# VDD_GND.net
KiCad netlist of a schematic drawn in Altium Designer
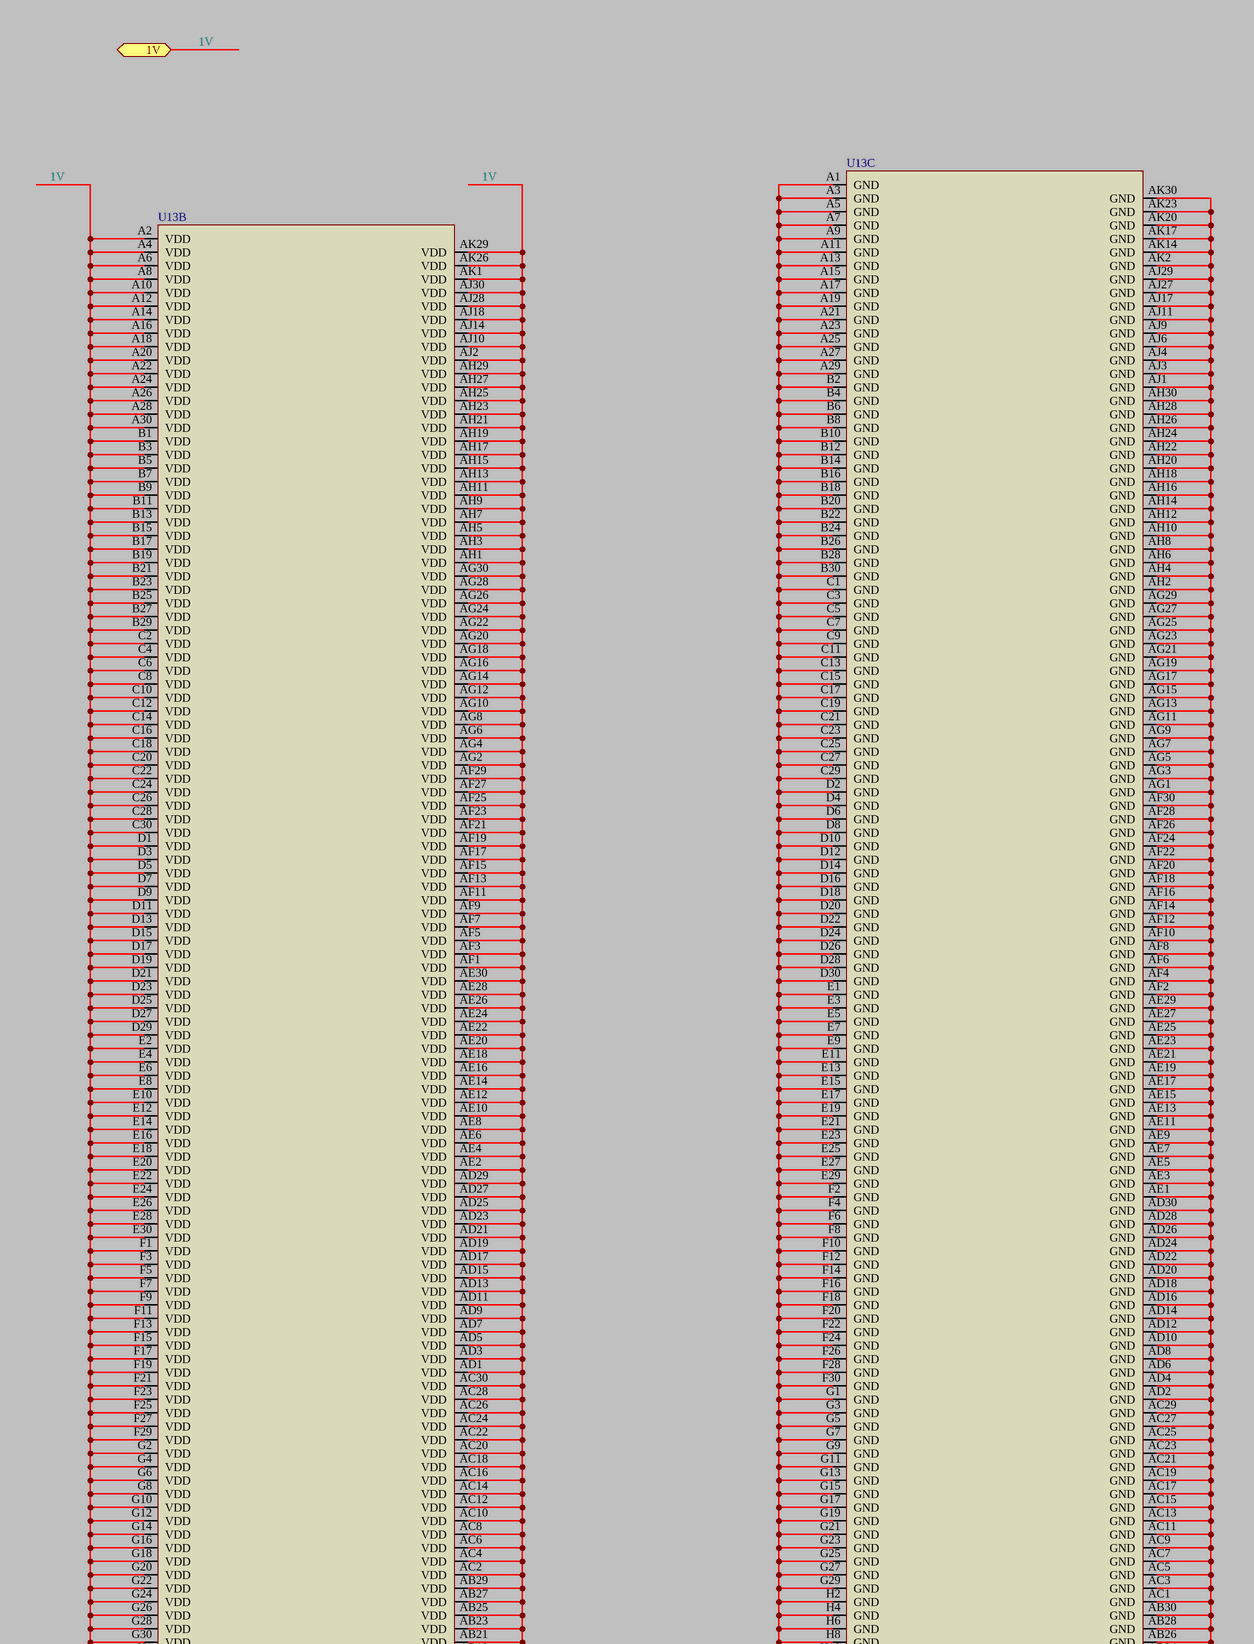
[diagram p0: VDD_GND.SchDoc, top left]
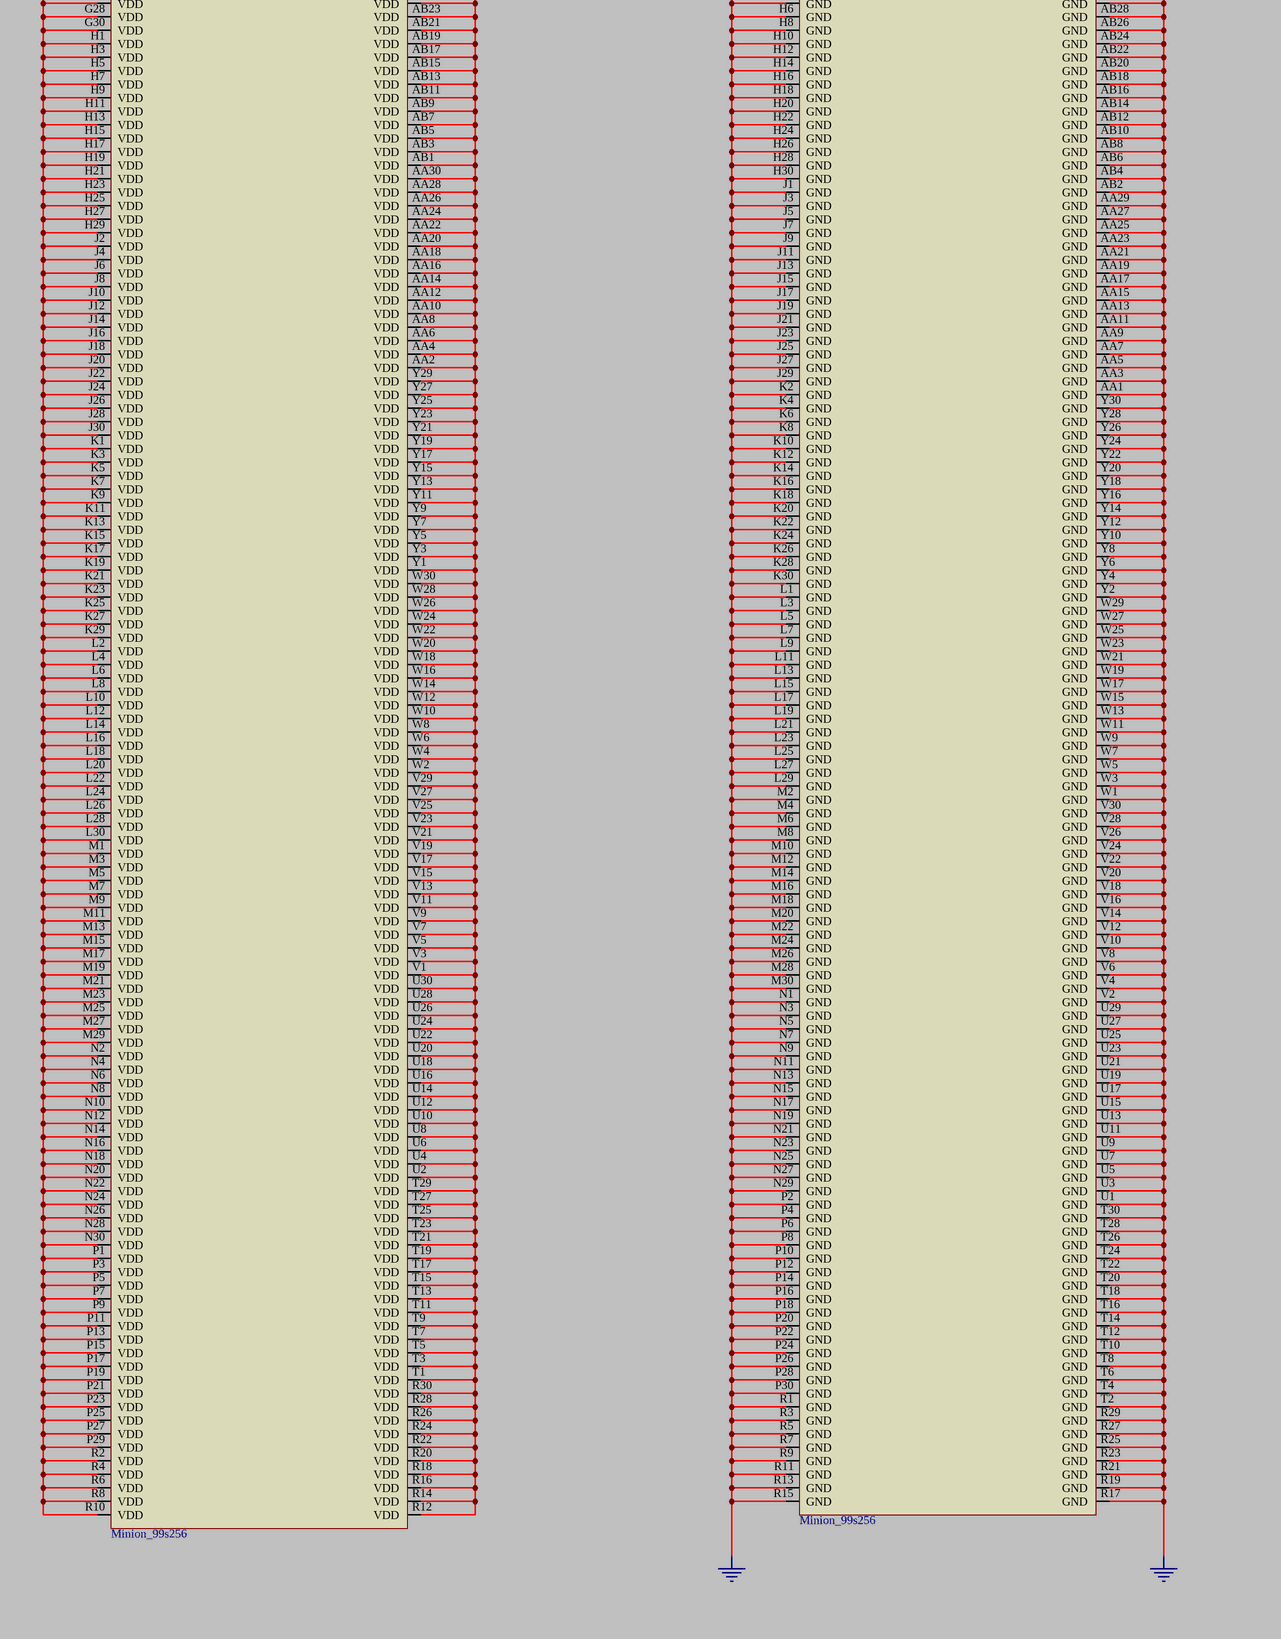
[diagram p1: VDD_GND.SchDoc, bottom left]
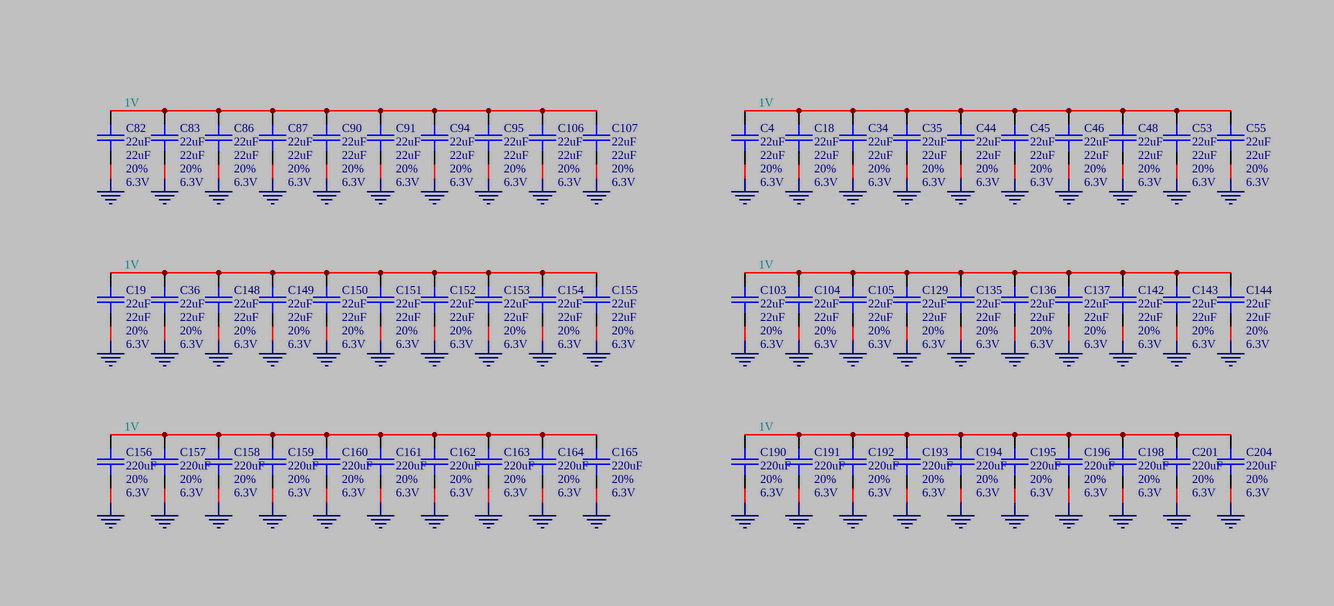
[diagram p2: VDD_GND.SchDoc, bottom middle]
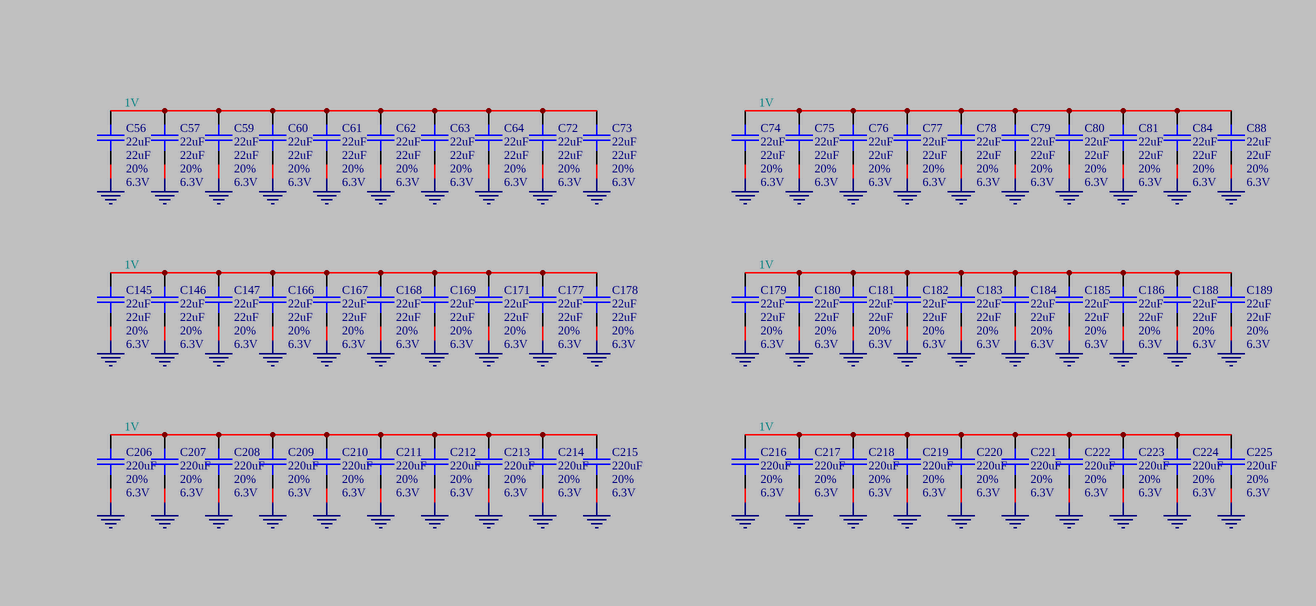
[diagram p3: VDD_GND.SchDoc, bottom right]

(export (version "E")
  (design (tool "Eeschema 10.0.6"))
  (components
    (comp (ref "C4")
      (value "22uF")
      (footprint "SMD_0805_CAPC2012X145N")
      (fields
        (field (name "DB_PART_NUMBER") "CAP000043686")
        (field (name "DB_VALUE") "22uF")
        (field (name "DB_TOLERANCE") "20%")
        (field (name "DB_VOLTAGE") "6.3V")
        (field (name "DB_MANUFACTURER_PART") "KEMET    C0805C226M9PAC")
        (field (name "DB_APPROVED_BY") "ISHIDDEN=T")
      )
      (libsource (lib "Database_Libs1") (part "C"))
    )
    (comp (ref "C18")
      (value "22uF")
      (footprint "SMD_0805_CAPC2012X145N")
      (fields
        (field (name "DB_PART_NUMBER") "CAP000043686")
        (field (name "DB_VALUE") "22uF")
        (field (name "DB_TOLERANCE") "20%")
        (field (name "DB_VOLTAGE") "6.3V")
        (field (name "DB_MANUFACTURER_PART") "KEMET    C0805C226M9PAC")
        (field (name "DB_APPROVED_BY") "ISHIDDEN=T")
      )
      (libsource (lib "Database_Libs1") (part "C"))
    )
    (comp (ref "C19")
      (value "22uF")
      (footprint "SMD_0805_CAPC2012X145N")
      (fields
        (field (name "DB_PART_NUMBER") "CAP000043686")
        (field (name "DB_VALUE") "22uF")
        (field (name "DB_TOLERANCE") "20%")
        (field (name "DB_VOLTAGE") "6.3V")
        (field (name "DB_MANUFACTURER_PART") "KEMET    C0805C226M9PAC")
        (field (name "DB_APPROVED_BY") "ISHIDDEN=T")
      )
      (libsource (lib "Database_Libs1") (part "C"))
    )
    (comp (ref "C34")
      (value "22uF")
      (footprint "SMD_0805_CAPC2012X145N")
      (fields
        (field (name "DB_PART_NUMBER") "CAP000043686")
        (field (name "DB_VALUE") "22uF")
        (field (name "DB_TOLERANCE") "20%")
        (field (name "DB_VOLTAGE") "6.3V")
        (field (name "DB_MANUFACTURER_PART") "KEMET    C0805C226M9PAC")
        (field (name "DB_APPROVED_BY") "ISHIDDEN=T")
      )
      (libsource (lib "Database_Libs1") (part "C"))
    )
    (comp (ref "C35")
      (value "22uF")
      (footprint "SMD_0805_CAPC2012X145N")
      (fields
        (field (name "DB_PART_NUMBER") "CAP000043686")
        (field (name "DB_VALUE") "22uF")
        (field (name "DB_TOLERANCE") "20%")
        (field (name "DB_VOLTAGE") "6.3V")
        (field (name "DB_MANUFACTURER_PART") "KEMET    C0805C226M9PAC")
        (field (name "DB_APPROVED_BY") "ISHIDDEN=T")
      )
      (libsource (lib "Database_Libs1") (part "C"))
    )
    (comp (ref "C36")
      (value "22uF")
      (footprint "SMD_0805_CAPC2012X145N")
      (fields
        (field (name "DB_PART_NUMBER") "CAP000043686")
        (field (name "DB_VALUE") "22uF")
        (field (name "DB_TOLERANCE") "20%")
        (field (name "DB_VOLTAGE") "6.3V")
        (field (name "DB_MANUFACTURER_PART") "KEMET    C0805C226M9PAC")
        (field (name "DB_APPROVED_BY") "ISHIDDEN=T")
      )
      (libsource (lib "Database_Libs1") (part "C"))
    )
    (comp (ref "C44")
      (value "22uF")
      (footprint "SMD_0805_CAPC2012X145N")
      (fields
        (field (name "DB_PART_NUMBER") "CAP000043686")
        (field (name "DB_VALUE") "22uF")
        (field (name "DB_TOLERANCE") "20%")
        (field (name "DB_VOLTAGE") "6.3V")
        (field (name "DB_MANUFACTURER_PART") "KEMET    C0805C226M9PAC")
        (field (name "DB_APPROVED_BY") "ISHIDDEN=T")
      )
      (libsource (lib "Database_Libs1") (part "C"))
    )
    (comp (ref "C45")
      (value "22uF")
      (footprint "SMD_0805_CAPC2012X145N")
      (fields
        (field (name "DB_PART_NUMBER") "CAP000043686")
        (field (name "DB_VALUE") "22uF")
        (field (name "DB_TOLERANCE") "20%")
        (field (name "DB_VOLTAGE") "6.3V")
        (field (name "DB_MANUFACTURER_PART") "KEMET    C0805C226M9PAC")
        (field (name "DB_APPROVED_BY") "ISHIDDEN=T")
      )
      (libsource (lib "Database_Libs1") (part "C"))
    )
    (comp (ref "C46")
      (value "22uF")
      (footprint "SMD_0805_CAPC2012X145N")
      (fields
        (field (name "DB_PART_NUMBER") "CAP000043686")
        (field (name "DB_VALUE") "22uF")
        (field (name "DB_TOLERANCE") "20%")
        (field (name "DB_VOLTAGE") "6.3V")
        (field (name "DB_MANUFACTURER_PART") "KEMET    C0805C226M9PAC")
        (field (name "DB_APPROVED_BY") "ISHIDDEN=T")
      )
      (libsource (lib "Database_Libs1") (part "C"))
    )
    (comp (ref "C48")
      (value "22uF")
      (footprint "SMD_0805_CAPC2012X145N")
      (fields
        (field (name "DB_PART_NUMBER") "CAP000043686")
        (field (name "DB_VALUE") "22uF")
        (field (name "DB_TOLERANCE") "20%")
        (field (name "DB_VOLTAGE") "6.3V")
        (field (name "DB_MANUFACTURER_PART") "KEMET    C0805C226M9PAC")
        (field (name "DB_APPROVED_BY") "ISHIDDEN=T")
      )
      (libsource (lib "Database_Libs1") (part "C"))
    )
    (comp (ref "C53")
      (value "22uF")
      (footprint "SMD_0805_CAPC2012X145N")
      (fields
        (field (name "DB_PART_NUMBER") "CAP000043686")
        (field (name "DB_VALUE") "22uF")
        (field (name "DB_TOLERANCE") "20%")
        (field (name "DB_VOLTAGE") "6.3V")
        (field (name "DB_MANUFACTURER_PART") "KEMET    C0805C226M9PAC")
        (field (name "DB_APPROVED_BY") "ISHIDDEN=T")
      )
      (libsource (lib "Database_Libs1") (part "C"))
    )
    (comp (ref "C55")
      (value "22uF")
      (footprint "SMD_0805_CAPC2012X145N")
      (fields
        (field (name "DB_PART_NUMBER") "CAP000043686")
        (field (name "DB_VALUE") "22uF")
        (field (name "DB_TOLERANCE") "20%")
        (field (name "DB_VOLTAGE") "6.3V")
        (field (name "DB_MANUFACTURER_PART") "KEMET    C0805C226M9PAC")
        (field (name "DB_APPROVED_BY") "ISHIDDEN=T")
      )
      (libsource (lib "Database_Libs1") (part "C"))
    )
    (comp (ref "C56")
      (value "22uF")
      (footprint "SMD_0805_CAPC2012X145N")
      (fields
        (field (name "DB_PART_NUMBER") "CAP000043686")
        (field (name "DB_VALUE") "22uF")
        (field (name "DB_TOLERANCE") "20%")
        (field (name "DB_VOLTAGE") "6.3V")
        (field (name "DB_MANUFACTURER_PART") "KEMET    C0805C226M9PAC")
        (field (name "DB_APPROVED_BY") "ISHIDDEN=T")
      )
      (libsource (lib "Database_Libs1") (part "C"))
    )
    (comp (ref "C57")
      (value "22uF")
      (footprint "SMD_0805_CAPC2012X145N")
      (fields
        (field (name "DB_PART_NUMBER") "CAP000043686")
        (field (name "DB_VALUE") "22uF")
        (field (name "DB_TOLERANCE") "20%")
        (field (name "DB_VOLTAGE") "6.3V")
        (field (name "DB_MANUFACTURER_PART") "KEMET    C0805C226M9PAC")
        (field (name "DB_APPROVED_BY") "ISHIDDEN=T")
      )
      (libsource (lib "Database_Libs1") (part "C"))
    )
    (comp (ref "C59")
      (value "22uF")
      (footprint "SMD_0805_CAPC2012X145N")
      (fields
        (field (name "DB_PART_NUMBER") "CAP000043686")
        (field (name "DB_VALUE") "22uF")
        (field (name "DB_TOLERANCE") "20%")
        (field (name "DB_VOLTAGE") "6.3V")
        (field (name "DB_MANUFACTURER_PART") "KEMET    C0805C226M9PAC")
        (field (name "DB_APPROVED_BY") "ISHIDDEN=T")
      )
      (libsource (lib "Database_Libs1") (part "C"))
    )
    (comp (ref "C60")
      (value "22uF")
      (footprint "SMD_0805_CAPC2012X145N")
      (fields
        (field (name "DB_PART_NUMBER") "CAP000043686")
        (field (name "DB_VALUE") "22uF")
        (field (name "DB_TOLERANCE") "20%")
        (field (name "DB_VOLTAGE") "6.3V")
        (field (name "DB_MANUFACTURER_PART") "KEMET    C0805C226M9PAC")
        (field (name "DB_APPROVED_BY") "ISHIDDEN=T")
      )
      (libsource (lib "Database_Libs1") (part "C"))
    )
    (comp (ref "C61")
      (value "22uF")
      (footprint "SMD_0805_CAPC2012X145N")
      (fields
        (field (name "DB_PART_NUMBER") "CAP000043686")
        (field (name "DB_VALUE") "22uF")
        (field (name "DB_TOLERANCE") "20%")
        (field (name "DB_VOLTAGE") "6.3V")
        (field (name "DB_MANUFACTURER_PART") "KEMET    C0805C226M9PAC")
        (field (name "DB_APPROVED_BY") "ISHIDDEN=T")
      )
      (libsource (lib "Database_Libs1") (part "C"))
    )
    (comp (ref "C62")
      (value "22uF")
      (footprint "SMD_0805_CAPC2012X145N")
      (fields
        (field (name "DB_PART_NUMBER") "CAP000043686")
        (field (name "DB_VALUE") "22uF")
        (field (name "DB_TOLERANCE") "20%")
        (field (name "DB_VOLTAGE") "6.3V")
        (field (name "DB_MANUFACTURER_PART") "KEMET    C0805C226M9PAC")
        (field (name "DB_APPROVED_BY") "ISHIDDEN=T")
      )
      (libsource (lib "Database_Libs1") (part "C"))
    )
    (comp (ref "C63")
      (value "22uF")
      (footprint "SMD_0805_CAPC2012X145N")
      (fields
        (field (name "DB_PART_NUMBER") "CAP000043686")
        (field (name "DB_VALUE") "22uF")
        (field (name "DB_TOLERANCE") "20%")
        (field (name "DB_VOLTAGE") "6.3V")
        (field (name "DB_MANUFACTURER_PART") "KEMET    C0805C226M9PAC")
        (field (name "DB_APPROVED_BY") "ISHIDDEN=T")
      )
      (libsource (lib "Database_Libs1") (part "C"))
    )
    (comp (ref "C64")
      (value "22uF")
      (footprint "SMD_0805_CAPC2012X145N")
      (fields
        (field (name "DB_PART_NUMBER") "CAP000043686")
        (field (name "DB_VALUE") "22uF")
        (field (name "DB_TOLERANCE") "20%")
        (field (name "DB_VOLTAGE") "6.3V")
        (field (name "DB_MANUFACTURER_PART") "KEMET    C0805C226M9PAC")
        (field (name "DB_APPROVED_BY") "ISHIDDEN=T")
      )
      (libsource (lib "Database_Libs1") (part "C"))
    )
    (comp (ref "C72")
      (value "22uF")
      (footprint "SMD_0805_CAPC2012X145N")
      (fields
        (field (name "DB_PART_NUMBER") "CAP000043686")
        (field (name "DB_VALUE") "22uF")
        (field (name "DB_TOLERANCE") "20%")
        (field (name "DB_VOLTAGE") "6.3V")
        (field (name "DB_MANUFACTURER_PART") "KEMET    C0805C226M9PAC")
        (field (name "DB_APPROVED_BY") "ISHIDDEN=T")
      )
      (libsource (lib "Database_Libs1") (part "C"))
    )
    (comp (ref "C73")
      (value "22uF")
      (footprint "SMD_0805_CAPC2012X145N")
      (fields
        (field (name "DB_PART_NUMBER") "CAP000043686")
        (field (name "DB_VALUE") "22uF")
        (field (name "DB_TOLERANCE") "20%")
        (field (name "DB_VOLTAGE") "6.3V")
        (field (name "DB_MANUFACTURER_PART") "KEMET    C0805C226M9PAC")
        (field (name "DB_APPROVED_BY") "ISHIDDEN=T")
      )
      (libsource (lib "Database_Libs1") (part "C"))
    )
    (comp (ref "C74")
      (value "22uF")
      (footprint "SMD_0805_CAPC2012X145N")
      (fields
        (field (name "DB_PART_NUMBER") "CAP000043686")
        (field (name "DB_VALUE") "22uF")
        (field (name "DB_TOLERANCE") "20%")
        (field (name "DB_VOLTAGE") "6.3V")
        (field (name "DB_MANUFACTURER_PART") "KEMET    C0805C226M9PAC")
        (field (name "DB_APPROVED_BY") "ISHIDDEN=T")
      )
      (libsource (lib "Database_Libs1") (part "C"))
    )
    (comp (ref "C75")
      (value "22uF")
      (footprint "SMD_0805_CAPC2012X145N")
      (fields
        (field (name "DB_PART_NUMBER") "CAP000043686")
        (field (name "DB_VALUE") "22uF")
        (field (name "DB_TOLERANCE") "20%")
        (field (name "DB_VOLTAGE") "6.3V")
        (field (name "DB_MANUFACTURER_PART") "KEMET    C0805C226M9PAC")
        (field (name "DB_APPROVED_BY") "ISHIDDEN=T")
      )
      (libsource (lib "Database_Libs1") (part "C"))
    )
    (comp (ref "C76")
      (value "22uF")
      (footprint "SMD_0805_CAPC2012X145N")
      (fields
        (field (name "DB_PART_NUMBER") "CAP000043686")
        (field (name "DB_VALUE") "22uF")
        (field (name "DB_TOLERANCE") "20%")
        (field (name "DB_VOLTAGE") "6.3V")
        (field (name "DB_MANUFACTURER_PART") "KEMET    C0805C226M9PAC")
        (field (name "DB_APPROVED_BY") "ISHIDDEN=T")
      )
      (libsource (lib "Database_Libs1") (part "C"))
    )
    (comp (ref "C77")
      (value "22uF")
      (footprint "SMD_0805_CAPC2012X145N")
      (fields
        (field (name "DB_PART_NUMBER") "CAP000043686")
        (field (name "DB_VALUE") "22uF")
        (field (name "DB_TOLERANCE") "20%")
        (field (name "DB_VOLTAGE") "6.3V")
        (field (name "DB_MANUFACTURER_PART") "KEMET    C0805C226M9PAC")
        (field (name "DB_APPROVED_BY") "ISHIDDEN=T")
      )
      (libsource (lib "Database_Libs1") (part "C"))
    )
    (comp (ref "C78")
      (value "22uF")
      (footprint "SMD_0805_CAPC2012X145N")
      (fields
        (field (name "DB_PART_NUMBER") "CAP000043686")
        (field (name "DB_VALUE") "22uF")
        (field (name "DB_TOLERANCE") "20%")
        (field (name "DB_VOLTAGE") "6.3V")
        (field (name "DB_MANUFACTURER_PART") "KEMET    C0805C226M9PAC")
        (field (name "DB_APPROVED_BY") "ISHIDDEN=T")
      )
      (libsource (lib "Database_Libs1") (part "C"))
    )
    (comp (ref "C79")
      (value "22uF")
      (footprint "SMD_0805_CAPC2012X145N")
      (fields
        (field (name "DB_PART_NUMBER") "CAP000043686")
        (field (name "DB_VALUE") "22uF")
        (field (name "DB_TOLERANCE") "20%")
        (field (name "DB_VOLTAGE") "6.3V")
        (field (name "DB_MANUFACTURER_PART") "KEMET    C0805C226M9PAC")
        (field (name "DB_APPROVED_BY") "ISHIDDEN=T")
      )
      (libsource (lib "Database_Libs1") (part "C"))
    )
    (comp (ref "C80")
      (value "22uF")
      (footprint "SMD_0805_CAPC2012X145N")
      (fields
        (field (name "DB_PART_NUMBER") "CAP000043686")
        (field (name "DB_VALUE") "22uF")
        (field (name "DB_TOLERANCE") "20%")
        (field (name "DB_VOLTAGE") "6.3V")
        (field (name "DB_MANUFACTURER_PART") "KEMET    C0805C226M9PAC")
        (field (name "DB_APPROVED_BY") "ISHIDDEN=T")
      )
      (libsource (lib "Database_Libs1") (part "C"))
    )
    (comp (ref "C81")
      (value "22uF")
      (footprint "SMD_0805_CAPC2012X145N")
      (fields
        (field (name "DB_PART_NUMBER") "CAP000043686")
        (field (name "DB_VALUE") "22uF")
        (field (name "DB_TOLERANCE") "20%")
        (field (name "DB_VOLTAGE") "6.3V")
        (field (name "DB_MANUFACTURER_PART") "KEMET    C0805C226M9PAC")
        (field (name "DB_APPROVED_BY") "ISHIDDEN=T")
      )
      (libsource (lib "Database_Libs1") (part "C"))
    )
    (comp (ref "C82")
      (value "22uF")
      (footprint "SMD_0805_CAPC2012X145N")
      (fields
        (field (name "DB_PART_NUMBER") "CAP000043686")
        (field (name "DB_VALUE") "22uF")
        (field (name "DB_TOLERANCE") "20%")
        (field (name "DB_VOLTAGE") "6.3V")
        (field (name "DB_MANUFACTURER_PART") "KEMET    C0805C226M9PAC")
        (field (name "DB_APPROVED_BY") "ISHIDDEN=T")
      )
      (libsource (lib "Database_Libs1") (part "C"))
    )
    (comp (ref "C83")
      (value "22uF")
      (footprint "SMD_0805_CAPC2012X145N")
      (fields
        (field (name "DB_PART_NUMBER") "CAP000043686")
        (field (name "DB_VALUE") "22uF")
        (field (name "DB_TOLERANCE") "20%")
        (field (name "DB_VOLTAGE") "6.3V")
        (field (name "DB_MANUFACTURER_PART") "KEMET    C0805C226M9PAC")
        (field (name "DB_APPROVED_BY") "ISHIDDEN=T")
      )
      (libsource (lib "Database_Libs1") (part "C"))
    )
    (comp (ref "C84")
      (value "22uF")
      (footprint "SMD_0805_CAPC2012X145N")
      (fields
        (field (name "DB_PART_NUMBER") "CAP000043686")
        (field (name "DB_VALUE") "22uF")
        (field (name "DB_TOLERANCE") "20%")
        (field (name "DB_VOLTAGE") "6.3V")
        (field (name "DB_MANUFACTURER_PART") "KEMET    C0805C226M9PAC")
        (field (name "DB_APPROVED_BY") "ISHIDDEN=T")
      )
      (libsource (lib "Database_Libs1") (part "C"))
    )
    (comp (ref "C86")
      (value "22uF")
      (footprint "SMD_0805_CAPC2012X145N")
      (fields
        (field (name "DB_PART_NUMBER") "CAP000043686")
        (field (name "DB_VALUE") "22uF")
        (field (name "DB_TOLERANCE") "20%")
        (field (name "DB_VOLTAGE") "6.3V")
        (field (name "DB_MANUFACTURER_PART") "KEMET    C0805C226M9PAC")
        (field (name "DB_APPROVED_BY") "ISHIDDEN=T")
      )
      (libsource (lib "Database_Libs1") (part "C"))
    )
    (comp (ref "C87")
      (value "22uF")
      (footprint "SMD_0805_CAPC2012X145N")
      (fields
        (field (name "DB_PART_NUMBER") "CAP000043686")
        (field (name "DB_VALUE") "22uF")
        (field (name "DB_TOLERANCE") "20%")
        (field (name "DB_VOLTAGE") "6.3V")
        (field (name "DB_MANUFACTURER_PART") "KEMET    C0805C226M9PAC")
        (field (name "DB_APPROVED_BY") "ISHIDDEN=T")
      )
      (libsource (lib "Database_Libs1") (part "C"))
    )
    (comp (ref "C88")
      (value "22uF")
      (footprint "SMD_0805_CAPC2012X145N")
      (fields
        (field (name "DB_PART_NUMBER") "CAP000043686")
        (field (name "DB_VALUE") "22uF")
        (field (name "DB_TOLERANCE") "20%")
        (field (name "DB_VOLTAGE") "6.3V")
        (field (name "DB_MANUFACTURER_PART") "KEMET    C0805C226M9PAC")
        (field (name "DB_APPROVED_BY") "ISHIDDEN=T")
      )
      (libsource (lib "Database_Libs1") (part "C"))
    )
    (comp (ref "C90")
      (value "22uF")
      (footprint "SMD_0805_CAPC2012X145N")
      (fields
        (field (name "DB_PART_NUMBER") "CAP000043686")
        (field (name "DB_VALUE") "22uF")
        (field (name "DB_TOLERANCE") "20%")
        (field (name "DB_VOLTAGE") "6.3V")
        (field (name "DB_MANUFACTURER_PART") "KEMET    C0805C226M9PAC")
        (field (name "DB_APPROVED_BY") "ISHIDDEN=T")
      )
      (libsource (lib "Database_Libs1") (part "C"))
    )
    (comp (ref "C91")
      (value "22uF")
      (footprint "SMD_0805_CAPC2012X145N")
      (fields
        (field (name "DB_PART_NUMBER") "CAP000043686")
        (field (name "DB_VALUE") "22uF")
        (field (name "DB_TOLERANCE") "20%")
        (field (name "DB_VOLTAGE") "6.3V")
        (field (name "DB_MANUFACTURER_PART") "KEMET    C0805C226M9PAC")
        (field (name "DB_APPROVED_BY") "ISHIDDEN=T")
      )
      (libsource (lib "Database_Libs1") (part "C"))
    )
    (comp (ref "C94")
      (value "22uF")
      (footprint "SMD_0805_CAPC2012X145N")
      (fields
        (field (name "DB_PART_NUMBER") "CAP000043686")
        (field (name "DB_VALUE") "22uF")
        (field (name "DB_TOLERANCE") "20%")
        (field (name "DB_VOLTAGE") "6.3V")
        (field (name "DB_MANUFACTURER_PART") "KEMET    C0805C226M9PAC")
        (field (name "DB_APPROVED_BY") "ISHIDDEN=T")
      )
      (libsource (lib "Database_Libs1") (part "C"))
    )
    (comp (ref "C95")
      (value "22uF")
      (footprint "SMD_0805_CAPC2012X145N")
      (fields
        (field (name "DB_PART_NUMBER") "CAP000043686")
        (field (name "DB_VALUE") "22uF")
        (field (name "DB_TOLERANCE") "20%")
        (field (name "DB_VOLTAGE") "6.3V")
        (field (name "DB_MANUFACTURER_PART") "KEMET    C0805C226M9PAC")
        (field (name "DB_APPROVED_BY") "ISHIDDEN=T")
      )
      (libsource (lib "Database_Libs1") (part "C"))
    )
    (comp (ref "C103")
      (value "22uF")
      (footprint "SMD_0805_CAPC2012X145N")
      (fields
        (field (name "DB_PART_NUMBER") "CAP000043686")
        (field (name "DB_VALUE") "22uF")
        (field (name "DB_TOLERANCE") "20%")
        (field (name "DB_VOLTAGE") "6.3V")
        (field (name "DB_MANUFACTURER_PART") "KEMET    C0805C226M9PAC")
        (field (name "DB_APPROVED_BY") "ISHIDDEN=T")
      )
      (libsource (lib "Database_Libs1") (part "C"))
    )
    (comp (ref "C104")
      (value "22uF")
      (footprint "SMD_0805_CAPC2012X145N")
      (fields
        (field (name "DB_PART_NUMBER") "CAP000043686")
        (field (name "DB_VALUE") "22uF")
        (field (name "DB_TOLERANCE") "20%")
        (field (name "DB_VOLTAGE") "6.3V")
        (field (name "DB_MANUFACTURER_PART") "KEMET    C0805C226M9PAC")
        (field (name "DB_APPROVED_BY") "ISHIDDEN=T")
      )
      (libsource (lib "Database_Libs1") (part "C"))
    )
    (comp (ref "C105")
      (value "22uF")
      (footprint "SMD_0805_CAPC2012X145N")
      (fields
        (field (name "DB_PART_NUMBER") "CAP000043686")
        (field (name "DB_VALUE") "22uF")
        (field (name "DB_TOLERANCE") "20%")
        (field (name "DB_VOLTAGE") "6.3V")
        (field (name "DB_MANUFACTURER_PART") "KEMET    C0805C226M9PAC")
        (field (name "DB_APPROVED_BY") "ISHIDDEN=T")
      )
      (libsource (lib "Database_Libs1") (part "C"))
    )
    (comp (ref "C106")
      (value "22uF")
      (footprint "SMD_0805_CAPC2012X145N")
      (fields
        (field (name "DB_PART_NUMBER") "CAP000043686")
        (field (name "DB_VALUE") "22uF")
        (field (name "DB_TOLERANCE") "20%")
        (field (name "DB_VOLTAGE") "6.3V")
        (field (name "DB_MANUFACTURER_PART") "KEMET    C0805C226M9PAC")
        (field (name "DB_APPROVED_BY") "ISHIDDEN=T")
      )
      (libsource (lib "Database_Libs1") (part "C"))
    )
    (comp (ref "C107")
      (value "22uF")
      (footprint "SMD_0805_CAPC2012X145N")
      (fields
        (field (name "DB_PART_NUMBER") "CAP000043686")
        (field (name "DB_VALUE") "22uF")
        (field (name "DB_TOLERANCE") "20%")
        (field (name "DB_VOLTAGE") "6.3V")
        (field (name "DB_MANUFACTURER_PART") "KEMET    C0805C226M9PAC")
        (field (name "DB_APPROVED_BY") "ISHIDDEN=T")
      )
      (libsource (lib "Database_Libs1") (part "C"))
    )
    (comp (ref "C129")
      (value "22uF")
      (footprint "SMD_0805_CAPC2012X145N")
      (fields
        (field (name "DB_PART_NUMBER") "CAP000043686")
        (field (name "DB_VALUE") "22uF")
        (field (name "DB_TOLERANCE") "20%")
        (field (name "DB_VOLTAGE") "6.3V")
        (field (name "DB_MANUFACTURER_PART") "KEMET    C0805C226M9PAC")
        (field (name "DB_APPROVED_BY") "ISHIDDEN=T")
      )
      (libsource (lib "Database_Libs1") (part "C"))
    )
    (comp (ref "C135")
      (value "22uF")
      (footprint "SMD_0805_CAPC2012X145N")
      (fields
        (field (name "DB_PART_NUMBER") "CAP000043686")
        (field (name "DB_VALUE") "22uF")
        (field (name "DB_TOLERANCE") "20%")
        (field (name "DB_VOLTAGE") "6.3V")
        (field (name "DB_MANUFACTURER_PART") "KEMET    C0805C226M9PAC")
        (field (name "DB_APPROVED_BY") "ISHIDDEN=T")
      )
      (libsource (lib "Database_Libs1") (part "C"))
    )
    (comp (ref "C136")
      (value "22uF")
      (footprint "SMD_0805_CAPC2012X145N")
      (fields
        (field (name "DB_PART_NUMBER") "CAP000043686")
        (field (name "DB_VALUE") "22uF")
        (field (name "DB_TOLERANCE") "20%")
        (field (name "DB_VOLTAGE") "6.3V")
        (field (name "DB_MANUFACTURER_PART") "KEMET    C0805C226M9PAC")
        (field (name "DB_APPROVED_BY") "ISHIDDEN=T")
      )
      (libsource (lib "Database_Libs1") (part "C"))
    )
    (comp (ref "C137")
      (value "22uF")
      (footprint "SMD_0805_CAPC2012X145N")
      (fields
        (field (name "DB_PART_NUMBER") "CAP000043686")
        (field (name "DB_VALUE") "22uF")
        (field (name "DB_TOLERANCE") "20%")
        (field (name "DB_VOLTAGE") "6.3V")
        (field (name "DB_MANUFACTURER_PART") "KEMET    C0805C226M9PAC")
        (field (name "DB_APPROVED_BY") "ISHIDDEN=T")
      )
      (libsource (lib "Database_Libs1") (part "C"))
    )
    (comp (ref "C142")
      (value "22uF")
      (footprint "SMD_0805_CAPC2012X145N")
      (fields
        (field (name "DB_PART_NUMBER") "CAP000043686")
        (field (name "DB_VALUE") "22uF")
        (field (name "DB_TOLERANCE") "20%")
        (field (name "DB_VOLTAGE") "6.3V")
        (field (name "DB_MANUFACTURER_PART") "KEMET    C0805C226M9PAC")
        (field (name "DB_APPROVED_BY") "ISHIDDEN=T")
      )
      (libsource (lib "Database_Libs1") (part "C"))
    )
    (comp (ref "C143")
      (value "22uF")
      (footprint "SMD_0805_CAPC2012X145N")
      (fields
        (field (name "DB_PART_NUMBER") "CAP000043686")
        (field (name "DB_VALUE") "22uF")
        (field (name "DB_TOLERANCE") "20%")
        (field (name "DB_VOLTAGE") "6.3V")
        (field (name "DB_MANUFACTURER_PART") "KEMET    C0805C226M9PAC")
        (field (name "DB_APPROVED_BY") "ISHIDDEN=T")
      )
      (libsource (lib "Database_Libs1") (part "C"))
    )
    (comp (ref "C144")
      (value "22uF")
      (footprint "SMD_0805_CAPC2012X145N")
      (fields
        (field (name "DB_PART_NUMBER") "CAP000043686")
        (field (name "DB_VALUE") "22uF")
        (field (name "DB_TOLERANCE") "20%")
        (field (name "DB_VOLTAGE") "6.3V")
        (field (name "DB_MANUFACTURER_PART") "KEMET    C0805C226M9PAC")
        (field (name "DB_APPROVED_BY") "ISHIDDEN=T")
      )
      (libsource (lib "Database_Libs1") (part "C"))
    )
    (comp (ref "C145")
      (value "22uF")
      (footprint "SMD_0805_CAPC2012X145N")
      (fields
        (field (name "DB_PART_NUMBER") "CAP000043686")
        (field (name "DB_VALUE") "22uF")
        (field (name "DB_TOLERANCE") "20%")
        (field (name "DB_VOLTAGE") "6.3V")
        (field (name "DB_MANUFACTURER_PART") "KEMET    C0805C226M9PAC")
        (field (name "DB_APPROVED_BY") "ISHIDDEN=T")
      )
      (libsource (lib "Database_Libs1") (part "C"))
    )
    (comp (ref "C146")
      (value "22uF")
      (footprint "SMD_0805_CAPC2012X145N")
      (fields
        (field (name "DB_PART_NUMBER") "CAP000043686")
        (field (name "DB_VALUE") "22uF")
        (field (name "DB_TOLERANCE") "20%")
        (field (name "DB_VOLTAGE") "6.3V")
        (field (name "DB_MANUFACTURER_PART") "KEMET    C0805C226M9PAC")
        (field (name "DB_APPROVED_BY") "ISHIDDEN=T")
      )
      (libsource (lib "Database_Libs1") (part "C"))
    )
    (comp (ref "C147")
      (value "22uF")
      (footprint "SMD_0805_CAPC2012X145N")
      (fields
        (field (name "DB_PART_NUMBER") "CAP000043686")
        (field (name "DB_VALUE") "22uF")
        (field (name "DB_TOLERANCE") "20%")
        (field (name "DB_VOLTAGE") "6.3V")
        (field (name "DB_MANUFACTURER_PART") "KEMET    C0805C226M9PAC")
        (field (name "DB_APPROVED_BY") "ISHIDDEN=T")
      )
      (libsource (lib "Database_Libs1") (part "C"))
    )
    (comp (ref "C148")
      (value "22uF")
      (footprint "SMD_0805_CAPC2012X145N")
      (fields
        (field (name "DB_PART_NUMBER") "CAP000043686")
        (field (name "DB_VALUE") "22uF")
        (field (name "DB_TOLERANCE") "20%")
        (field (name "DB_VOLTAGE") "6.3V")
        (field (name "DB_MANUFACTURER_PART") "KEMET    C0805C226M9PAC")
        (field (name "DB_APPROVED_BY") "ISHIDDEN=T")
      )
      (libsource (lib "Database_Libs1") (part "C"))
    )
    (comp (ref "C149")
      (value "22uF")
      (footprint "SMD_0805_CAPC2012X145N")
      (fields
        (field (name "DB_PART_NUMBER") "CAP000043686")
        (field (name "DB_VALUE") "22uF")
        (field (name "DB_TOLERANCE") "20%")
        (field (name "DB_VOLTAGE") "6.3V")
        (field (name "DB_MANUFACTURER_PART") "KEMET    C0805C226M9PAC")
        (field (name "DB_APPROVED_BY") "ISHIDDEN=T")
      )
      (libsource (lib "Database_Libs1") (part "C"))
    )
    (comp (ref "C150")
      (value "22uF")
      (footprint "SMD_0805_CAPC2012X145N")
      (fields
        (field (name "DB_PART_NUMBER") "CAP000043686")
        (field (name "DB_VALUE") "22uF")
        (field (name "DB_TOLERANCE") "20%")
        (field (name "DB_VOLTAGE") "6.3V")
        (field (name "DB_MANUFACTURER_PART") "KEMET    C0805C226M9PAC")
        (field (name "DB_APPROVED_BY") "ISHIDDEN=T")
      )
      (libsource (lib "Database_Libs1") (part "C"))
    )
    (comp (ref "C151")
      (value "22uF")
      (footprint "SMD_0805_CAPC2012X145N")
      (fields
        (field (name "DB_PART_NUMBER") "CAP000043686")
        (field (name "DB_VALUE") "22uF")
        (field (name "DB_TOLERANCE") "20%")
        (field (name "DB_VOLTAGE") "6.3V")
        (field (name "DB_MANUFACTURER_PART") "KEMET    C0805C226M9PAC")
        (field (name "DB_APPROVED_BY") "ISHIDDEN=T")
      )
      (libsource (lib "Database_Libs1") (part "C"))
    )
    (comp (ref "C152")
      (value "22uF")
      (footprint "SMD_0805_CAPC2012X145N")
      (fields
        (field (name "DB_PART_NUMBER") "CAP000043686")
        (field (name "DB_VALUE") "22uF")
        (field (name "DB_TOLERANCE") "20%")
        (field (name "DB_VOLTAGE") "6.3V")
        (field (name "DB_MANUFACTURER_PART") "KEMET    C0805C226M9PAC")
        (field (name "DB_APPROVED_BY") "ISHIDDEN=T")
      )
      (libsource (lib "Database_Libs1") (part "C"))
    )
    (comp (ref "C153")
      (value "22uF")
      (footprint "SMD_0805_CAPC2012X145N")
      (fields
        (field (name "DB_PART_NUMBER") "CAP000043686")
        (field (name "DB_VALUE") "22uF")
        (field (name "DB_TOLERANCE") "20%")
        (field (name "DB_VOLTAGE") "6.3V")
        (field (name "DB_MANUFACTURER_PART") "KEMET    C0805C226M9PAC")
        (field (name "DB_APPROVED_BY") "ISHIDDEN=T")
      )
      (libsource (lib "Database_Libs1") (part "C"))
    )
    (comp (ref "C154")
      (value "22uF")
      (footprint "SMD_0805_CAPC2012X145N")
      (fields
        (field (name "DB_PART_NUMBER") "CAP000043686")
        (field (name "DB_VALUE") "22uF")
        (field (name "DB_TOLERANCE") "20%")
        (field (name "DB_VOLTAGE") "6.3V")
        (field (name "DB_MANUFACTURER_PART") "KEMET    C0805C226M9PAC")
        (field (name "DB_APPROVED_BY") "ISHIDDEN=T")
      )
      (libsource (lib "Database_Libs1") (part "C"))
    )
    (comp (ref "C155")
      (value "22uF")
      (footprint "SMD_0805_CAPC2012X145N")
      (fields
        (field (name "DB_PART_NUMBER") "CAP000043686")
        (field (name "DB_VALUE") "22uF")
        (field (name "DB_TOLERANCE") "20%")
        (field (name "DB_VOLTAGE") "6.3V")
        (field (name "DB_MANUFACTURER_PART") "KEMET    C0805C226M9PAC")
        (field (name "DB_APPROVED_BY") "ISHIDDEN=T")
      )
      (libsource (lib "Database_Libs1") (part "C"))
    )
    (comp (ref "C156")
      (value "220uF")
      (footprint "SMD_1210_CAPC3225X279N")
      (fields
        (field (name "DB_PART_NUMBER") "CAP000047355")
        (field (name "DB_VALUE") "220uF")
        (field (name "DB_TOLERANCE") "20%")
        (field (name "DB_VOLTAGE") "6.3V")
        (field (name "DB_MANUFACTURER_PART") "SAMSUNG    CL32A227MQVNNNE")
        (field (name "DB_APPROVED_BY") "VSN")
      )
      (libsource (lib "Database_Libs1") (part "C"))
    )
    (comp (ref "C157")
      (value "220uF")
      (footprint "SMD_1210_CAPC3225X279N")
      (fields
        (field (name "DB_PART_NUMBER") "CAP000047355")
        (field (name "DB_VALUE") "220uF")
        (field (name "DB_TOLERANCE") "20%")
        (field (name "DB_VOLTAGE") "6.3V")
        (field (name "DB_MANUFACTURER_PART") "SAMSUNG    CL32A227MQVNNNE")
        (field (name "DB_APPROVED_BY") "VSN")
      )
      (libsource (lib "Database_Libs1") (part "C"))
    )
    (comp (ref "C158")
      (value "220uF")
      (footprint "SMD_1210_CAPC3225X279N")
      (fields
        (field (name "DB_PART_NUMBER") "CAP000047355")
        (field (name "DB_VALUE") "220uF")
        (field (name "DB_TOLERANCE") "20%")
        (field (name "DB_VOLTAGE") "6.3V")
        (field (name "DB_MANUFACTURER_PART") "SAMSUNG    CL32A227MQVNNNE")
        (field (name "DB_APPROVED_BY") "VSN")
      )
      (libsource (lib "Database_Libs1") (part "C"))
    )
    (comp (ref "C159")
      (value "220uF")
      (footprint "SMD_1210_CAPC3225X279N")
      (fields
        (field (name "DB_PART_NUMBER") "CAP000047355")
        (field (name "DB_VALUE") "220uF")
        (field (name "DB_TOLERANCE") "20%")
        (field (name "DB_VOLTAGE") "6.3V")
        (field (name "DB_MANUFACTURER_PART") "SAMSUNG    CL32A227MQVNNNE")
        (field (name "DB_APPROVED_BY") "VSN")
      )
      (libsource (lib "Database_Libs1") (part "C"))
    )
    (comp (ref "C160")
      (value "220uF")
      (footprint "SMD_1210_CAPC3225X279N")
      (fields
        (field (name "DB_PART_NUMBER") "CAP000047355")
        (field (name "DB_VALUE") "220uF")
        (field (name "DB_TOLERANCE") "20%")
        (field (name "DB_VOLTAGE") "6.3V")
        (field (name "DB_MANUFACTURER_PART") "SAMSUNG    CL32A227MQVNNNE")
        (field (name "DB_APPROVED_BY") "VSN")
      )
      (libsource (lib "Database_Libs1") (part "C"))
    )
    (comp (ref "C161")
      (value "220uF")
      (footprint "SMD_1210_CAPC3225X279N")
      (fields
        (field (name "DB_PART_NUMBER") "CAP000047355")
        (field (name "DB_VALUE") "220uF")
        (field (name "DB_TOLERANCE") "20%")
        (field (name "DB_VOLTAGE") "6.3V")
        (field (name "DB_MANUFACTURER_PART") "SAMSUNG    CL32A227MQVNNNE")
        (field (name "DB_APPROVED_BY") "VSN")
      )
      (libsource (lib "Database_Libs1") (part "C"))
    )
    (comp (ref "C162")
      (value "220uF")
      (footprint "SMD_1210_CAPC3225X279N")
      (fields
        (field (name "DB_PART_NUMBER") "CAP000047355")
        (field (name "DB_VALUE") "220uF")
        (field (name "DB_TOLERANCE") "20%")
        (field (name "DB_VOLTAGE") "6.3V")
        (field (name "DB_MANUFACTURER_PART") "SAMSUNG    CL32A227MQVNNNE")
        (field (name "DB_APPROVED_BY") "VSN")
      )
      (libsource (lib "Database_Libs1") (part "C"))
    )
    (comp (ref "C163")
      (value "220uF")
      (footprint "SMD_1210_CAPC3225X279N")
      (fields
        (field (name "DB_PART_NUMBER") "CAP000047355")
        (field (name "DB_VALUE") "220uF")
        (field (name "DB_TOLERANCE") "20%")
        (field (name "DB_VOLTAGE") "6.3V")
        (field (name "DB_MANUFACTURER_PART") "SAMSUNG    CL32A227MQVNNNE")
        (field (name "DB_APPROVED_BY") "VSN")
      )
      (libsource (lib "Database_Libs1") (part "C"))
    )
    (comp (ref "C164")
      (value "220uF")
      (footprint "SMD_1210_CAPC3225X279N")
      (fields
        (field (name "DB_PART_NUMBER") "CAP000047355")
        (field (name "DB_VALUE") "220uF")
        (field (name "DB_TOLERANCE") "20%")
        (field (name "DB_VOLTAGE") "6.3V")
        (field (name "DB_MANUFACTURER_PART") "SAMSUNG    CL32A227MQVNNNE")
        (field (name "DB_APPROVED_BY") "VSN")
      )
      (libsource (lib "Database_Libs1") (part "C"))
    )
    (comp (ref "C165")
      (value "220uF")
      (footprint "SMD_1210_CAPC3225X279N")
      (fields
        (field (name "DB_PART_NUMBER") "CAP000047355")
        (field (name "DB_VALUE") "220uF")
        (field (name "DB_TOLERANCE") "20%")
        (field (name "DB_VOLTAGE") "6.3V")
        (field (name "DB_MANUFACTURER_PART") "SAMSUNG    CL32A227MQVNNNE")
        (field (name "DB_APPROVED_BY") "VSN")
      )
      (libsource (lib "Database_Libs1") (part "C"))
    )
    (comp (ref "C166")
      (value "22uF")
      (footprint "SMD_0805_CAPC2012X145N")
      (fields
        (field (name "DB_PART_NUMBER") "CAP000043686")
        (field (name "DB_VALUE") "22uF")
        (field (name "DB_TOLERANCE") "20%")
        (field (name "DB_VOLTAGE") "6.3V")
        (field (name "DB_MANUFACTURER_PART") "KEMET    C0805C226M9PAC")
        (field (name "DB_APPROVED_BY") "ISHIDDEN=T")
      )
      (libsource (lib "Database_Libs1") (part "C"))
    )
    (comp (ref "C167")
      (value "22uF")
      (footprint "SMD_0805_CAPC2012X145N")
      (fields
        (field (name "DB_PART_NUMBER") "CAP000043686")
        (field (name "DB_VALUE") "22uF")
        (field (name "DB_TOLERANCE") "20%")
        (field (name "DB_VOLTAGE") "6.3V")
        (field (name "DB_MANUFACTURER_PART") "KEMET    C0805C226M9PAC")
        (field (name "DB_APPROVED_BY") "ISHIDDEN=T")
      )
      (libsource (lib "Database_Libs1") (part "C"))
    )
    (comp (ref "C168")
      (value "22uF")
      (footprint "SMD_0805_CAPC2012X145N")
      (fields
        (field (name "DB_PART_NUMBER") "CAP000043686")
        (field (name "DB_VALUE") "22uF")
        (field (name "DB_TOLERANCE") "20%")
        (field (name "DB_VOLTAGE") "6.3V")
        (field (name "DB_MANUFACTURER_PART") "KEMET    C0805C226M9PAC")
        (field (name "DB_APPROVED_BY") "ISHIDDEN=T")
      )
      (libsource (lib "Database_Libs1") (part "C"))
    )
    (comp (ref "C169")
      (value "22uF")
      (footprint "SMD_0805_CAPC2012X145N")
      (fields
        (field (name "DB_PART_NUMBER") "CAP000043686")
        (field (name "DB_VALUE") "22uF")
        (field (name "DB_TOLERANCE") "20%")
        (field (name "DB_VOLTAGE") "6.3V")
        (field (name "DB_MANUFACTURER_PART") "KEMET    C0805C226M9PAC")
        (field (name "DB_APPROVED_BY") "ISHIDDEN=T")
      )
      (libsource (lib "Database_Libs1") (part "C"))
    )
    (comp (ref "C171")
      (value "22uF")
      (footprint "SMD_0805_CAPC2012X145N")
      (fields
        (field (name "DB_PART_NUMBER") "CAP000043686")
        (field (name "DB_VALUE") "22uF")
        (field (name "DB_TOLERANCE") "20%")
        (field (name "DB_VOLTAGE") "6.3V")
        (field (name "DB_MANUFACTURER_PART") "KEMET    C0805C226M9PAC")
        (field (name "DB_APPROVED_BY") "ISHIDDEN=T")
      )
      (libsource (lib "Database_Libs1") (part "C"))
    )
    (comp (ref "C177")
      (value "22uF")
      (footprint "SMD_0805_CAPC2012X145N")
      (fields
        (field (name "DB_PART_NUMBER") "CAP000043686")
        (field (name "DB_VALUE") "22uF")
        (field (name "DB_TOLERANCE") "20%")
        (field (name "DB_VOLTAGE") "6.3V")
        (field (name "DB_MANUFACTURER_PART") "KEMET    C0805C226M9PAC")
        (field (name "DB_APPROVED_BY") "ISHIDDEN=T")
      )
      (libsource (lib "Database_Libs1") (part "C"))
    )
    (comp (ref "C178")
      (value "22uF")
      (footprint "SMD_0805_CAPC2012X145N")
      (fields
        (field (name "DB_PART_NUMBER") "CAP000043686")
        (field (name "DB_VALUE") "22uF")
        (field (name "DB_TOLERANCE") "20%")
        (field (name "DB_VOLTAGE") "6.3V")
        (field (name "DB_MANUFACTURER_PART") "KEMET    C0805C226M9PAC")
        (field (name "DB_APPROVED_BY") "ISHIDDEN=T")
      )
      (libsource (lib "Database_Libs1") (part "C"))
    )
    (comp (ref "C179")
      (value "22uF")
      (footprint "SMD_0805_CAPC2012X145N")
      (fields
        (field (name "DB_PART_NUMBER") "CAP000043686")
        (field (name "DB_VALUE") "22uF")
        (field (name "DB_TOLERANCE") "20%")
        (field (name "DB_VOLTAGE") "6.3V")
        (field (name "DB_MANUFACTURER_PART") "KEMET    C0805C226M9PAC")
        (field (name "DB_APPROVED_BY") "ISHIDDEN=T")
      )
      (libsource (lib "Database_Libs1") (part "C"))
    )
    (comp (ref "C180")
      (value "22uF")
      (footprint "SMD_0805_CAPC2012X145N")
      (fields
        (field (name "DB_PART_NUMBER") "CAP000043686")
        (field (name "DB_VALUE") "22uF")
        (field (name "DB_TOLERANCE") "20%")
        (field (name "DB_VOLTAGE") "6.3V")
        (field (name "DB_MANUFACTURER_PART") "KEMET    C0805C226M9PAC")
        (field (name "DB_APPROVED_BY") "ISHIDDEN=T")
      )
      (libsource (lib "Database_Libs1") (part "C"))
    )
    (comp (ref "C181")
      (value "22uF")
      (footprint "SMD_0805_CAPC2012X145N")
      (fields
        (field (name "DB_PART_NUMBER") "CAP000043686")
        (field (name "DB_VALUE") "22uF")
        (field (name "DB_TOLERANCE") "20%")
        (field (name "DB_VOLTAGE") "6.3V")
        (field (name "DB_MANUFACTURER_PART") "KEMET    C0805C226M9PAC")
        (field (name "DB_APPROVED_BY") "ISHIDDEN=T")
      )
      (libsource (lib "Database_Libs1") (part "C"))
    )
    (comp (ref "C182")
      (value "22uF")
      (footprint "SMD_0805_CAPC2012X145N")
      (fields
        (field (name "DB_PART_NUMBER") "CAP000043686")
        (field (name "DB_VALUE") "22uF")
        (field (name "DB_TOLERANCE") "20%")
        (field (name "DB_VOLTAGE") "6.3V")
        (field (name "DB_MANUFACTURER_PART") "KEMET    C0805C226M9PAC")
        (field (name "DB_APPROVED_BY") "ISHIDDEN=T")
      )
      (libsource (lib "Database_Libs1") (part "C"))
    )
    (comp (ref "C183")
      (value "22uF")
      (footprint "SMD_0805_CAPC2012X145N")
      (fields
        (field (name "DB_PART_NUMBER") "CAP000043686")
        (field (name "DB_VALUE") "22uF")
        (field (name "DB_TOLERANCE") "20%")
        (field (name "DB_VOLTAGE") "6.3V")
        (field (name "DB_MANUFACTURER_PART") "KEMET    C0805C226M9PAC")
        (field (name "DB_APPROVED_BY") "ISHIDDEN=T")
      )
      (libsource (lib "Database_Libs1") (part "C"))
    )
    (comp (ref "C184")
      (value "22uF")
      (footprint "SMD_0805_CAPC2012X145N")
      (fields
        (field (name "DB_PART_NUMBER") "CAP000043686")
        (field (name "DB_VALUE") "22uF")
        (field (name "DB_TOLERANCE") "20%")
        (field (name "DB_VOLTAGE") "6.3V")
        (field (name "DB_MANUFACTURER_PART") "KEMET    C0805C226M9PAC")
        (field (name "DB_APPROVED_BY") "ISHIDDEN=T")
      )
      (libsource (lib "Database_Libs1") (part "C"))
    )
    (comp (ref "C185")
      (value "22uF")
      (footprint "SMD_0805_CAPC2012X145N")
      (fields
        (field (name "DB_PART_NUMBER") "CAP000043686")
        (field (name "DB_VALUE") "22uF")
        (field (name "DB_TOLERANCE") "20%")
        (field (name "DB_VOLTAGE") "6.3V")
        (field (name "DB_MANUFACTURER_PART") "KEMET    C0805C226M9PAC")
        (field (name "DB_APPROVED_BY") "ISHIDDEN=T")
      )
      (libsource (lib "Database_Libs1") (part "C"))
    )
    (comp (ref "C186")
      (value "22uF")
      (footprint "SMD_0805_CAPC2012X145N")
      (fields
        (field (name "DB_PART_NUMBER") "CAP000043686")
        (field (name "DB_VALUE") "22uF")
        (field (name "DB_TOLERANCE") "20%")
        (field (name "DB_VOLTAGE") "6.3V")
        (field (name "DB_MANUFACTURER_PART") "KEMET    C0805C226M9PAC")
        (field (name "DB_APPROVED_BY") "ISHIDDEN=T")
      )
      (libsource (lib "Database_Libs1") (part "C"))
    )
    (comp (ref "C188")
      (value "22uF")
      (footprint "SMD_0805_CAPC2012X145N")
      (fields
        (field (name "DB_PART_NUMBER") "CAP000043686")
        (field (name "DB_VALUE") "22uF")
        (field (name "DB_TOLERANCE") "20%")
        (field (name "DB_VOLTAGE") "6.3V")
        (field (name "DB_MANUFACTURER_PART") "KEMET    C0805C226M9PAC")
        (field (name "DB_APPROVED_BY") "ISHIDDEN=T")
      )
      (libsource (lib "Database_Libs1") (part "C"))
    )
    (comp (ref "C189")
      (value "22uF")
      (footprint "SMD_0805_CAPC2012X145N")
      (fields
        (field (name "DB_PART_NUMBER") "CAP000043686")
        (field (name "DB_VALUE") "22uF")
        (field (name "DB_TOLERANCE") "20%")
        (field (name "DB_VOLTAGE") "6.3V")
        (field (name "DB_MANUFACTURER_PART") "KEMET    C0805C226M9PAC")
        (field (name "DB_APPROVED_BY") "ISHIDDEN=T")
      )
      (libsource (lib "Database_Libs1") (part "C"))
    )
    (comp (ref "C190")
      (value "220uF")
      (footprint "SMD_1210_CAPC3225X279N")
      (fields
        (field (name "DB_PART_NUMBER") "CAP000047355")
        (field (name "DB_VALUE") "220uF")
        (field (name "DB_TOLERANCE") "20%")
        (field (name "DB_VOLTAGE") "6.3V")
        (field (name "DB_MANUFACTURER_PART") "SAMSUNG    CL32A227MQVNNNE")
        (field (name "DB_APPROVED_BY") "VSN")
      )
      (libsource (lib "Database_Libs1") (part "C"))
    )
    (comp (ref "C191")
      (value "220uF")
      (footprint "SMD_1210_CAPC3225X279N")
      (fields
        (field (name "DB_PART_NUMBER") "CAP000047355")
        (field (name "DB_VALUE") "220uF")
        (field (name "DB_TOLERANCE") "20%")
        (field (name "DB_VOLTAGE") "6.3V")
        (field (name "DB_MANUFACTURER_PART") "SAMSUNG    CL32A227MQVNNNE")
        (field (name "DB_APPROVED_BY") "VSN")
      )
      (libsource (lib "Database_Libs1") (part "C"))
    )
    (comp (ref "C192")
      (value "220uF")
      (footprint "SMD_1210_CAPC3225X279N")
      (fields
        (field (name "DB_PART_NUMBER") "CAP000047355")
        (field (name "DB_VALUE") "220uF")
        (field (name "DB_TOLERANCE") "20%")
        (field (name "DB_VOLTAGE") "6.3V")
        (field (name "DB_MANUFACTURER_PART") "SAMSUNG    CL32A227MQVNNNE")
        (field (name "DB_APPROVED_BY") "VSN")
      )
      (libsource (lib "Database_Libs1") (part "C"))
    )
    (comp (ref "C193")
      (value "220uF")
      (footprint "SMD_1210_CAPC3225X279N")
      (fields
        (field (name "DB_PART_NUMBER") "CAP000047355")
        (field (name "DB_VALUE") "220uF")
        (field (name "DB_TOLERANCE") "20%")
        (field (name "DB_VOLTAGE") "6.3V")
        (field (name "DB_MANUFACTURER_PART") "SAMSUNG    CL32A227MQVNNNE")
        (field (name "DB_APPROVED_BY") "VSN")
      )
      (libsource (lib "Database_Libs1") (part "C"))
    )
    (comp (ref "C194")
      (value "220uF")
      (footprint "SMD_1210_CAPC3225X279N")
      (fields
        (field (name "DB_PART_NUMBER") "CAP000047355")
        (field (name "DB_VALUE") "220uF")
        (field (name "DB_TOLERANCE") "20%")
        (field (name "DB_VOLTAGE") "6.3V")
        (field (name "DB_MANUFACTURER_PART") "SAMSUNG    CL32A227MQVNNNE")
        (field (name "DB_APPROVED_BY") "VSN")
      )
      (libsource (lib "Database_Libs1") (part "C"))
    )
    (comp (ref "C195")
      (value "220uF")
      (footprint "SMD_1210_CAPC3225X279N")
      (fields
        (field (name "DB_PART_NUMBER") "CAP000047355")
        (field (name "DB_VALUE") "220uF")
        (field (name "DB_TOLERANCE") "20%")
        (field (name "DB_VOLTAGE") "6.3V")
        (field (name "DB_MANUFACTURER_PART") "SAMSUNG    CL32A227MQVNNNE")
        (field (name "DB_APPROVED_BY") "VSN")
      )
      (libsource (lib "Database_Libs1") (part "C"))
    )
    (comp (ref "C196")
      (value "220uF")
      (footprint "SMD_1210_CAPC3225X279N")
      (fields
        (field (name "DB_PART_NUMBER") "CAP000047355")
        (field (name "DB_VALUE") "220uF")
        (field (name "DB_TOLERANCE") "20%")
        (field (name "DB_VOLTAGE") "6.3V")
        (field (name "DB_MANUFACTURER_PART") "SAMSUNG    CL32A227MQVNNNE")
        (field (name "DB_APPROVED_BY") "VSN")
      )
      (libsource (lib "Database_Libs1") (part "C"))
    )
    (comp (ref "C198")
      (value "220uF")
      (footprint "SMD_1210_CAPC3225X279N")
      (fields
        (field (name "DB_PART_NUMBER") "CAP000047355")
        (field (name "DB_VALUE") "220uF")
        (field (name "DB_TOLERANCE") "20%")
        (field (name "DB_VOLTAGE") "6.3V")
        (field (name "DB_MANUFACTURER_PART") "SAMSUNG    CL32A227MQVNNNE")
        (field (name "DB_APPROVED_BY") "VSN")
      )
      (libsource (lib "Database_Libs1") (part "C"))
    )
    (comp (ref "C201")
      (value "220uF")
      (footprint "SMD_1210_CAPC3225X279N")
      (fields
        (field (name "DB_PART_NUMBER") "CAP000047355")
        (field (name "DB_VALUE") "220uF")
        (field (name "DB_TOLERANCE") "20%")
        (field (name "DB_VOLTAGE") "6.3V")
        (field (name "DB_MANUFACTURER_PART") "SAMSUNG    CL32A227MQVNNNE")
        (field (name "DB_APPROVED_BY") "VSN")
      )
      (libsource (lib "Database_Libs1") (part "C"))
    )
    (comp (ref "C204")
      (value "220uF")
      (footprint "SMD_1210_CAPC3225X279N")
      (fields
        (field (name "DB_PART_NUMBER") "CAP000047355")
        (field (name "DB_VALUE") "220uF")
        (field (name "DB_TOLERANCE") "20%")
        (field (name "DB_VOLTAGE") "6.3V")
        (field (name "DB_MANUFACTURER_PART") "SAMSUNG    CL32A227MQVNNNE")
        (field (name "DB_APPROVED_BY") "VSN")
      )
      (libsource (lib "Database_Libs1") (part "C"))
    )
    (comp (ref "C206")
      (value "220uF")
      (footprint "SMD_1210_CAPC3225X279N")
      (fields
        (field (name "DB_PART_NUMBER") "CAP000047355")
        (field (name "DB_VALUE") "220uF")
        (field (name "DB_TOLERANCE") "20%")
        (field (name "DB_VOLTAGE") "6.3V")
        (field (name "DB_MANUFACTURER_PART") "SAMSUNG    CL32A227MQVNNNE")
        (field (name "DB_APPROVED_BY") "VSN")
      )
      (libsource (lib "Database_Libs1") (part "C"))
    )
    (comp (ref "C207")
      (value "220uF")
      (footprint "SMD_1210_CAPC3225X279N")
      (fields
        (field (name "DB_PART_NUMBER") "CAP000047355")
        (field (name "DB_VALUE") "220uF")
        (field (name "DB_TOLERANCE") "20%")
        (field (name "DB_VOLTAGE") "6.3V")
        (field (name "DB_MANUFACTURER_PART") "SAMSUNG    CL32A227MQVNNNE")
        (field (name "DB_APPROVED_BY") "VSN")
      )
      (libsource (lib "Database_Libs1") (part "C"))
    )
    (comp (ref "C208")
      (value "220uF")
      (footprint "SMD_1210_CAPC3225X279N")
      (fields
        (field (name "DB_PART_NUMBER") "CAP000047355")
        (field (name "DB_VALUE") "220uF")
        (field (name "DB_TOLERANCE") "20%")
        (field (name "DB_VOLTAGE") "6.3V")
        (field (name "DB_MANUFACTURER_PART") "SAMSUNG    CL32A227MQVNNNE")
        (field (name "DB_APPROVED_BY") "VSN")
      )
      (libsource (lib "Database_Libs1") (part "C"))
    )
    (comp (ref "C209")
      (value "220uF")
      (footprint "SMD_1210_CAPC3225X279N")
      (fields
        (field (name "DB_PART_NUMBER") "CAP000047355")
        (field (name "DB_VALUE") "220uF")
        (field (name "DB_TOLERANCE") "20%")
        (field (name "DB_VOLTAGE") "6.3V")
        (field (name "DB_MANUFACTURER_PART") "SAMSUNG    CL32A227MQVNNNE")
        (field (name "DB_APPROVED_BY") "VSN")
      )
      (libsource (lib "Database_Libs1") (part "C"))
    )
    (comp (ref "C210")
      (value "220uF")
      (footprint "SMD_1210_CAPC3225X279N")
      (fields
        (field (name "DB_PART_NUMBER") "CAP000047355")
        (field (name "DB_VALUE") "220uF")
        (field (name "DB_TOLERANCE") "20%")
        (field (name "DB_VOLTAGE") "6.3V")
        (field (name "DB_MANUFACTURER_PART") "SAMSUNG    CL32A227MQVNNNE")
        (field (name "DB_APPROVED_BY") "VSN")
      )
      (libsource (lib "Database_Libs1") (part "C"))
    )
    (comp (ref "C211")
      (value "220uF")
      (footprint "SMD_1210_CAPC3225X279N")
      (fields
        (field (name "DB_PART_NUMBER") "CAP000047355")
        (field (name "DB_VALUE") "220uF")
        (field (name "DB_TOLERANCE") "20%")
        (field (name "DB_VOLTAGE") "6.3V")
        (field (name "DB_MANUFACTURER_PART") "SAMSUNG    CL32A227MQVNNNE")
        (field (name "DB_APPROVED_BY") "VSN")
      )
      (libsource (lib "Database_Libs1") (part "C"))
    )
    (comp (ref "C212")
      (value "220uF")
      (footprint "SMD_1210_CAPC3225X279N")
      (fields
        (field (name "DB_PART_NUMBER") "CAP000047355")
        (field (name "DB_VALUE") "220uF")
        (field (name "DB_TOLERANCE") "20%")
        (field (name "DB_VOLTAGE") "6.3V")
        (field (name "DB_MANUFACTURER_PART") "SAMSUNG    CL32A227MQVNNNE")
        (field (name "DB_APPROVED_BY") "VSN")
      )
      (libsource (lib "Database_Libs1") (part "C"))
    )
    (comp (ref "C213")
      (value "220uF")
      (footprint "SMD_1210_CAPC3225X279N")
      (fields
        (field (name "DB_PART_NUMBER") "CAP000047355")
        (field (name "DB_VALUE") "220uF")
        (field (name "DB_TOLERANCE") "20%")
        (field (name "DB_VOLTAGE") "6.3V")
        (field (name "DB_MANUFACTURER_PART") "SAMSUNG    CL32A227MQVNNNE")
        (field (name "DB_APPROVED_BY") "VSN")
      )
      (libsource (lib "Database_Libs1") (part "C"))
    )
    (comp (ref "C214")
      (value "220uF")
      (footprint "SMD_1210_CAPC3225X279N")
      (fields
        (field (name "DB_PART_NUMBER") "CAP000047355")
        (field (name "DB_VALUE") "220uF")
        (field (name "DB_TOLERANCE") "20%")
        (field (name "DB_VOLTAGE") "6.3V")
        (field (name "DB_MANUFACTURER_PART") "SAMSUNG    CL32A227MQVNNNE")
        (field (name "DB_APPROVED_BY") "VSN")
      )
      (libsource (lib "Database_Libs1") (part "C"))
    )
    (comp (ref "C215")
      (value "220uF")
      (footprint "SMD_1210_CAPC3225X279N")
      (fields
        (field (name "DB_PART_NUMBER") "CAP000047355")
        (field (name "DB_VALUE") "220uF")
        (field (name "DB_TOLERANCE") "20%")
        (field (name "DB_VOLTAGE") "6.3V")
        (field (name "DB_MANUFACTURER_PART") "SAMSUNG    CL32A227MQVNNNE")
        (field (name "DB_APPROVED_BY") "VSN")
      )
      (libsource (lib "Database_Libs1") (part "C"))
    )
    (comp (ref "C216")
      (value "220uF")
      (footprint "SMD_1210_CAPC3225X279N")
      (fields
        (field (name "DB_PART_NUMBER") "CAP000047355")
        (field (name "DB_VALUE") "220uF")
        (field (name "DB_TOLERANCE") "20%")
        (field (name "DB_VOLTAGE") "6.3V")
        (field (name "DB_MANUFACTURER_PART") "SAMSUNG    CL32A227MQVNNNE")
        (field (name "DB_APPROVED_BY") "VSN")
      )
      (libsource (lib "Database_Libs1") (part "C"))
    )
    (comp (ref "C217")
      (value "220uF")
      (footprint "SMD_1210_CAPC3225X279N")
      (fields
        (field (name "DB_PART_NUMBER") "CAP000047355")
        (field (name "DB_VALUE") "220uF")
        (field (name "DB_TOLERANCE") "20%")
        (field (name "DB_VOLTAGE") "6.3V")
        (field (name "DB_MANUFACTURER_PART") "SAMSUNG    CL32A227MQVNNNE")
        (field (name "DB_APPROVED_BY") "VSN")
      )
      (libsource (lib "Database_Libs1") (part "C"))
    )
    (comp (ref "C218")
      (value "220uF")
      (footprint "SMD_1210_CAPC3225X279N")
      (fields
        (field (name "DB_PART_NUMBER") "CAP000047355")
        (field (name "DB_VALUE") "220uF")
        (field (name "DB_TOLERANCE") "20%")
        (field (name "DB_VOLTAGE") "6.3V")
        (field (name "DB_MANUFACTURER_PART") "SAMSUNG    CL32A227MQVNNNE")
        (field (name "DB_APPROVED_BY") "VSN")
      )
      (libsource (lib "Database_Libs1") (part "C"))
    )
    (comp (ref "C219")
      (value "220uF")
      (footprint "SMD_1210_CAPC3225X279N")
      (fields
        (field (name "DB_PART_NUMBER") "CAP000047355")
        (field (name "DB_VALUE") "220uF")
        (field (name "DB_TOLERANCE") "20%")
        (field (name "DB_VOLTAGE") "6.3V")
        (field (name "DB_MANUFACTURER_PART") "SAMSUNG    CL32A227MQVNNNE")
        (field (name "DB_APPROVED_BY") "VSN")
      )
      (libsource (lib "Database_Libs1") (part "C"))
    )
    (comp (ref "C220")
      (value "220uF")
      (footprint "SMD_1210_CAPC3225X279N")
      (fields
        (field (name "DB_PART_NUMBER") "CAP000047355")
        (field (name "DB_VALUE") "220uF")
        (field (name "DB_TOLERANCE") "20%")
        (field (name "DB_VOLTAGE") "6.3V")
        (field (name "DB_MANUFACTURER_PART") "SAMSUNG    CL32A227MQVNNNE")
        (field (name "DB_APPROVED_BY") "VSN")
      )
      (libsource (lib "Database_Libs1") (part "C"))
    )
    (comp (ref "C221")
      (value "220uF")
      (footprint "SMD_1210_CAPC3225X279N")
      (fields
        (field (name "DB_PART_NUMBER") "CAP000047355")
        (field (name "DB_VALUE") "220uF")
        (field (name "DB_TOLERANCE") "20%")
        (field (name "DB_VOLTAGE") "6.3V")
        (field (name "DB_MANUFACTURER_PART") "SAMSUNG    CL32A227MQVNNNE")
        (field (name "DB_APPROVED_BY") "VSN")
      )
      (libsource (lib "Database_Libs1") (part "C"))
    )
    (comp (ref "C222")
      (value "220uF")
      (footprint "SMD_1210_CAPC3225X279N")
      (fields
        (field (name "DB_PART_NUMBER") "CAP000047355")
        (field (name "DB_VALUE") "220uF")
        (field (name "DB_TOLERANCE") "20%")
        (field (name "DB_VOLTAGE") "6.3V")
        (field (name "DB_MANUFACTURER_PART") "SAMSUNG    CL32A227MQVNNNE")
        (field (name "DB_APPROVED_BY") "VSN")
      )
      (libsource (lib "Database_Libs1") (part "C"))
    )
    (comp (ref "C223")
      (value "220uF")
      (footprint "SMD_1210_CAPC3225X279N")
      (fields
        (field (name "DB_PART_NUMBER") "CAP000047355")
        (field (name "DB_VALUE") "220uF")
        (field (name "DB_TOLERANCE") "20%")
        (field (name "DB_VOLTAGE") "6.3V")
        (field (name "DB_MANUFACTURER_PART") "SAMSUNG    CL32A227MQVNNNE")
        (field (name "DB_APPROVED_BY") "VSN")
      )
      (libsource (lib "Database_Libs1") (part "C"))
    )
    (comp (ref "C224")
      (value "220uF")
      (footprint "SMD_1210_CAPC3225X279N")
      (fields
        (field (name "DB_PART_NUMBER") "CAP000047355")
        (field (name "DB_VALUE") "220uF")
        (field (name "DB_TOLERANCE") "20%")
        (field (name "DB_VOLTAGE") "6.3V")
        (field (name "DB_MANUFACTURER_PART") "SAMSUNG    CL32A227MQVNNNE")
        (field (name "DB_APPROVED_BY") "VSN")
      )
      (libsource (lib "Database_Libs1") (part "C"))
    )
    (comp (ref "C225")
      (value "220uF")
      (footprint "SMD_1210_CAPC3225X279N")
      (fields
        (field (name "DB_PART_NUMBER") "CAP000047355")
        (field (name "DB_VALUE") "220uF")
        (field (name "DB_TOLERANCE") "20%")
        (field (name "DB_VOLTAGE") "6.3V")
        (field (name "DB_MANUFACTURER_PART") "SAMSUNG    CL32A227MQVNNNE")
        (field (name "DB_APPROVED_BY") "VSN")
      )
      (libsource (lib "Database_Libs1") (part "C"))
    )
    (comp (ref "U13")
      (value "Minion_99s256")
      (footprint "SMD_BGA900C80P30X30")
      (libsource (lib "BitCoin") (part "Minion_99s256"))
    )
  )
  (nets
    (net (code "1") (name "/1V") (class "Default")
      (node (ref "C103") (pin "2") (pinfunction "2_2") (pintype "passive"))
      (node (ref "C104") (pin "2") (pinfunction "2_2") (pintype "passive"))
      (node (ref "C105") (pin "2") (pinfunction "2_2") (pintype "passive"))
      (node (ref "C106") (pin "2") (pinfunction "2_2") (pintype "passive"))
      (node (ref "C107") (pin "2") (pinfunction "2_2") (pintype "passive"))
      (node (ref "C129") (pin "2") (pinfunction "2_2") (pintype "passive"))
      (node (ref "C135") (pin "2") (pinfunction "2_2") (pintype "passive"))
      (node (ref "C136") (pin "2") (pinfunction "2_2") (pintype "passive"))
      (node (ref "C137") (pin "2") (pinfunction "2_2") (pintype "passive"))
      (node (ref "C142") (pin "2") (pinfunction "2_2") (pintype "passive"))
      (node (ref "C143") (pin "2") (pinfunction "2_2") (pintype "passive"))
      (node (ref "C144") (pin "2") (pinfunction "2_2") (pintype "passive"))
      (node (ref "C145") (pin "2") (pinfunction "2_2") (pintype "passive"))
      (node (ref "C146") (pin "2") (pinfunction "2_2") (pintype "passive"))
      (node (ref "C147") (pin "2") (pinfunction "2_2") (pintype "passive"))
      (node (ref "C148") (pin "2") (pinfunction "2_2") (pintype "passive"))
      (node (ref "C149") (pin "2") (pinfunction "2_2") (pintype "passive"))
      (node (ref "C150") (pin "2") (pinfunction "2_2") (pintype "passive"))
      (node (ref "C151") (pin "2") (pinfunction "2_2") (pintype "passive"))
      (node (ref "C152") (pin "2") (pinfunction "2_2") (pintype "passive"))
      (node (ref "C153") (pin "2") (pinfunction "2_2") (pintype "passive"))
      (node (ref "C154") (pin "2") (pinfunction "2_2") (pintype "passive"))
      (node (ref "C155") (pin "2") (pinfunction "2_2") (pintype "passive"))
      (node (ref "C156") (pin "2") (pinfunction "2_2") (pintype "passive"))
      (node (ref "C157") (pin "2") (pinfunction "2_2") (pintype "passive"))
      (node (ref "C158") (pin "2") (pinfunction "2_2") (pintype "passive"))
      (node (ref "C159") (pin "2") (pinfunction "2_2") (pintype "passive"))
      (node (ref "C160") (pin "2") (pinfunction "2_2") (pintype "passive"))
      (node (ref "C161") (pin "2") (pinfunction "2_2") (pintype "passive"))
      (node (ref "C162") (pin "2") (pinfunction "2_2") (pintype "passive"))
      (node (ref "C163") (pin "2") (pinfunction "2_2") (pintype "passive"))
      (node (ref "C164") (pin "2") (pinfunction "2_2") (pintype "passive"))
      (node (ref "C165") (pin "2") (pinfunction "2_2") (pintype "passive"))
      (node (ref "C166") (pin "2") (pinfunction "2_2") (pintype "passive"))
      (node (ref "C167") (pin "2") (pinfunction "2_2") (pintype "passive"))
      (node (ref "C168") (pin "2") (pinfunction "2_2") (pintype "passive"))
      (node (ref "C169") (pin "2") (pinfunction "2_2") (pintype "passive"))
      (node (ref "C171") (pin "2") (pinfunction "2_2") (pintype "passive"))
      (node (ref "C177") (pin "2") (pinfunction "2_2") (pintype "passive"))
      (node (ref "C178") (pin "2") (pinfunction "2_2") (pintype "passive"))
      (node (ref "C179") (pin "2") (pinfunction "2_2") (pintype "passive"))
      (node (ref "C18") (pin "2") (pinfunction "2_2") (pintype "passive"))
      (node (ref "C180") (pin "2") (pinfunction "2_2") (pintype "passive"))
      (node (ref "C181") (pin "2") (pinfunction "2_2") (pintype "passive"))
      (node (ref "C182") (pin "2") (pinfunction "2_2") (pintype "passive"))
      (node (ref "C183") (pin "2") (pinfunction "2_2") (pintype "passive"))
      (node (ref "C184") (pin "2") (pinfunction "2_2") (pintype "passive"))
      (node (ref "C185") (pin "2") (pinfunction "2_2") (pintype "passive"))
      (node (ref "C186") (pin "2") (pinfunction "2_2") (pintype "passive"))
      (node (ref "C188") (pin "2") (pinfunction "2_2") (pintype "passive"))
      (node (ref "C189") (pin "2") (pinfunction "2_2") (pintype "passive"))
      (node (ref "C19") (pin "2") (pinfunction "2_2") (pintype "passive"))
      (node (ref "C190") (pin "2") (pinfunction "2_2") (pintype "passive"))
      (node (ref "C191") (pin "2") (pinfunction "2_2") (pintype "passive"))
      (node (ref "C192") (pin "2") (pinfunction "2_2") (pintype "passive"))
      (node (ref "C193") (pin "2") (pinfunction "2_2") (pintype "passive"))
      (node (ref "C194") (pin "2") (pinfunction "2_2") (pintype "passive"))
      (node (ref "C195") (pin "2") (pinfunction "2_2") (pintype "passive"))
      (node (ref "C196") (pin "2") (pinfunction "2_2") (pintype "passive"))
      (node (ref "C198") (pin "2") (pinfunction "2_2") (pintype "passive"))
      (node (ref "C201") (pin "2") (pinfunction "2_2") (pintype "passive"))
      (node (ref "C204") (pin "2") (pinfunction "2_2") (pintype "passive"))
      (node (ref "C206") (pin "2") (pinfunction "2_2") (pintype "passive"))
      (node (ref "C207") (pin "2") (pinfunction "2_2") (pintype "passive"))
      (node (ref "C208") (pin "2") (pinfunction "2_2") (pintype "passive"))
      (node (ref "C209") (pin "2") (pinfunction "2_2") (pintype "passive"))
      (node (ref "C210") (pin "2") (pinfunction "2_2") (pintype "passive"))
      (node (ref "C211") (pin "2") (pinfunction "2_2") (pintype "passive"))
      (node (ref "C212") (pin "2") (pinfunction "2_2") (pintype "passive"))
      (node (ref "C213") (pin "2") (pinfunction "2_2") (pintype "passive"))
      (node (ref "C214") (pin "2") (pinfunction "2_2") (pintype "passive"))
      (node (ref "C215") (pin "2") (pinfunction "2_2") (pintype "passive"))
      (node (ref "C216") (pin "2") (pinfunction "2_2") (pintype "passive"))
      (node (ref "C217") (pin "2") (pinfunction "2_2") (pintype "passive"))
      (node (ref "C218") (pin "2") (pinfunction "2_2") (pintype "passive"))
      (node (ref "C219") (pin "2") (pinfunction "2_2") (pintype "passive"))
      (node (ref "C220") (pin "2") (pinfunction "2_2") (pintype "passive"))
      (node (ref "C221") (pin "2") (pinfunction "2_2") (pintype "passive"))
      (node (ref "C222") (pin "2") (pinfunction "2_2") (pintype "passive"))
      (node (ref "C223") (pin "2") (pinfunction "2_2") (pintype "passive"))
      (node (ref "C224") (pin "2") (pinfunction "2_2") (pintype "passive"))
      (node (ref "C225") (pin "2") (pinfunction "2_2") (pintype "passive"))
      (node (ref "C34") (pin "2") (pinfunction "2_2") (pintype "passive"))
      (node (ref "C35") (pin "2") (pinfunction "2_2") (pintype "passive"))
      (node (ref "C36") (pin "2") (pinfunction "2_2") (pintype "passive"))
      (node (ref "C4") (pin "2") (pinfunction "2_2") (pintype "passive"))
      (node (ref "C44") (pin "2") (pinfunction "2_2") (pintype "passive"))
      (node (ref "C45") (pin "2") (pinfunction "2_2") (pintype "passive"))
      (node (ref "C46") (pin "2") (pinfunction "2_2") (pintype "passive"))
      (node (ref "C48") (pin "2") (pinfunction "2_2") (pintype "passive"))
      (node (ref "C53") (pin "2") (pinfunction "2_2") (pintype "passive"))
      (node (ref "C55") (pin "2") (pinfunction "2_2") (pintype "passive"))
      (node (ref "C56") (pin "2") (pinfunction "2_2") (pintype "passive"))
      (node (ref "C57") (pin "2") (pinfunction "2_2") (pintype "passive"))
      (node (ref "C59") (pin "2") (pinfunction "2_2") (pintype "passive"))
      (node (ref "C60") (pin "2") (pinfunction "2_2") (pintype "passive"))
      (node (ref "C61") (pin "2") (pinfunction "2_2") (pintype "passive"))
      (node (ref "C62") (pin "2") (pinfunction "2_2") (pintype "passive"))
      (node (ref "C63") (pin "2") (pinfunction "2_2") (pintype "passive"))
      (node (ref "C64") (pin "2") (pinfunction "2_2") (pintype "passive"))
      (node (ref "C72") (pin "2") (pinfunction "2_2") (pintype "passive"))
      (node (ref "C73") (pin "2") (pinfunction "2_2") (pintype "passive"))
      (node (ref "C74") (pin "2") (pinfunction "2_2") (pintype "passive"))
      (node (ref "C75") (pin "2") (pinfunction "2_2") (pintype "passive"))
      (node (ref "C76") (pin "2") (pinfunction "2_2") (pintype "passive"))
      (node (ref "C77") (pin "2") (pinfunction "2_2") (pintype "passive"))
      (node (ref "C78") (pin "2") (pinfunction "2_2") (pintype "passive"))
      (node (ref "C79") (pin "2") (pinfunction "2_2") (pintype "passive"))
      (node (ref "C80") (pin "2") (pinfunction "2_2") (pintype "passive"))
      (node (ref "C81") (pin "2") (pinfunction "2_2") (pintype "passive"))
      (node (ref "C82") (pin "2") (pinfunction "2_2") (pintype "passive"))
      (node (ref "C83") (pin "2") (pinfunction "2_2") (pintype "passive"))
      (node (ref "C84") (pin "2") (pinfunction "2_2") (pintype "passive"))
      (node (ref "C86") (pin "2") (pinfunction "2_2") (pintype "passive"))
      (node (ref "C87") (pin "2") (pinfunction "2_2") (pintype "passive"))
      (node (ref "C88") (pin "2") (pinfunction "2_2") (pintype "passive"))
      (node (ref "C90") (pin "2") (pinfunction "2_2") (pintype "passive"))
      (node (ref "C91") (pin "2") (pinfunction "2_2") (pintype "passive"))
      (node (ref "C94") (pin "2") (pinfunction "2_2") (pintype "passive"))
      (node (ref "C95") (pin "2") (pinfunction "2_2") (pintype "passive"))
      (node (ref "U13") (pin "A10") (pinfunction "VDD_A10") (pintype "passive"))
      (node (ref "U13") (pin "A12") (pinfunction "VDD_A12") (pintype "passive"))
      (node (ref "U13") (pin "A14") (pinfunction "VDD_A14") (pintype "passive"))
      (node (ref "U13") (pin "A16") (pinfunction "VDD_A16") (pintype "passive"))
      (node (ref "U13") (pin "A18") (pinfunction "VDD_A18") (pintype "passive"))
      (node (ref "U13") (pin "A2") (pinfunction "VDD_A2") (pintype "passive"))
      (node (ref "U13") (pin "A20") (pinfunction "VDD_A20") (pintype "passive"))
      (node (ref "U13") (pin "A22") (pinfunction "VDD_A22") (pintype "passive"))
      (node (ref "U13") (pin "A24") (pinfunction "VDD_A24") (pintype "passive"))
      (node (ref "U13") (pin "A26") (pinfunction "VDD_A26") (pintype "passive"))
      (node (ref "U13") (pin "A28") (pinfunction "VDD_A28") (pintype "passive"))
      (node (ref "U13") (pin "A30") (pinfunction "VDD_A30") (pintype "passive"))
      (node (ref "U13") (pin "A4") (pinfunction "VDD_A4") (pintype "passive"))
      (node (ref "U13") (pin "A6") (pinfunction "VDD_A6") (pintype "passive"))
      (node (ref "U13") (pin "A8") (pinfunction "VDD_A8") (pintype "passive"))
      (node (ref "U13") (pin "AA10") (pinfunction "VDD_AA10") (pintype "passive"))
      (node (ref "U13") (pin "AA12") (pinfunction "VDD_AA12") (pintype "passive"))
      (node (ref "U13") (pin "AA14") (pinfunction "VDD_AA14") (pintype "passive"))
      (node (ref "U13") (pin "AA16") (pinfunction "VDD_AA16") (pintype "passive"))
      (node (ref "U13") (pin "AA18") (pinfunction "VDD_AA18") (pintype "passive"))
      (node (ref "U13") (pin "AA2") (pinfunction "VDD_AA2") (pintype "passive"))
      (node (ref "U13") (pin "AA20") (pinfunction "VDD_AA20") (pintype "passive"))
      (node (ref "U13") (pin "AA22") (pinfunction "VDD_AA22") (pintype "passive"))
      (node (ref "U13") (pin "AA24") (pinfunction "VDD_AA24") (pintype "passive"))
      (node (ref "U13") (pin "AA26") (pinfunction "VDD_AA26") (pintype "passive"))
      (node (ref "U13") (pin "AA28") (pinfunction "VDD_AA28") (pintype "passive"))
      (node (ref "U13") (pin "AA30") (pinfunction "VDD_AA30") (pintype "passive"))
      (node (ref "U13") (pin "AA4") (pinfunction "VDD_AA4") (pintype "passive"))
      (node (ref "U13") (pin "AA6") (pinfunction "VDD_AA6") (pintype "passive"))
      (node (ref "U13") (pin "AA8") (pinfunction "VDD_AA8") (pintype "passive"))
      (node (ref "U13") (pin "AB1") (pinfunction "VDD_AB1") (pintype "passive"))
      (node (ref "U13") (pin "AB11") (pinfunction "VDD_AB11") (pintype "passive"))
      (node (ref "U13") (pin "AB13") (pinfunction "VDD_AB13") (pintype "passive"))
      (node (ref "U13") (pin "AB15") (pinfunction "VDD_AB15") (pintype "passive"))
      (node (ref "U13") (pin "AB17") (pinfunction "VDD_AB17") (pintype "passive"))
      (node (ref "U13") (pin "AB19") (pinfunction "VDD_AB19") (pintype "passive"))
      (node (ref "U13") (pin "AB21") (pinfunction "VDD_AB21") (pintype "passive"))
      (node (ref "U13") (pin "AB23") (pinfunction "VDD_AB23") (pintype "passive"))
      (node (ref "U13") (pin "AB25") (pinfunction "VDD_AB25") (pintype "passive"))
      (node (ref "U13") (pin "AB27") (pinfunction "VDD_AB27") (pintype "passive"))
      (node (ref "U13") (pin "AB29") (pinfunction "VDD_AB29") (pintype "passive"))
      (node (ref "U13") (pin "AB3") (pinfunction "VDD_AB3") (pintype "passive"))
      (node (ref "U13") (pin "AB5") (pinfunction "VDD_AB5") (pintype "passive"))
      (node (ref "U13") (pin "AB7") (pinfunction "VDD_AB7") (pintype "passive"))
      (node (ref "U13") (pin "AB9") (pinfunction "VDD_AB9") (pintype "passive"))
      (node (ref "U13") (pin "AC10") (pinfunction "VDD_AC10") (pintype "passive"))
      (node (ref "U13") (pin "AC12") (pinfunction "VDD_AC12") (pintype "passive"))
      (node (ref "U13") (pin "AC14") (pinfunction "VDD_AC14") (pintype "passive"))
      (node (ref "U13") (pin "AC16") (pinfunction "VDD_AC16") (pintype "passive"))
      (node (ref "U13") (pin "AC18") (pinfunction "VDD_AC18") (pintype "passive"))
      (node (ref "U13") (pin "AC2") (pinfunction "VDD_AC2") (pintype "passive"))
      (node (ref "U13") (pin "AC20") (pinfunction "VDD_AC20") (pintype "passive"))
      (node (ref "U13") (pin "AC22") (pinfunction "VDD_AC22") (pintype "passive"))
      (node (ref "U13") (pin "AC24") (pinfunction "VDD_AC24") (pintype "passive"))
      (node (ref "U13") (pin "AC26") (pinfunction "VDD_AC26") (pintype "passive"))
      (node (ref "U13") (pin "AC28") (pinfunction "VDD_AC28") (pintype "passive"))
      (node (ref "U13") (pin "AC30") (pinfunction "VDD_AC30") (pintype "passive"))
      (node (ref "U13") (pin "AC4") (pinfunction "VDD_AC4") (pintype "passive"))
      (node (ref "U13") (pin "AC6") (pinfunction "VDD_AC6") (pintype "passive"))
      (node (ref "U13") (pin "AC8") (pinfunction "VDD_AC8") (pintype "passive"))
      (node (ref "U13") (pin "AD1") (pinfunction "VDD_AD1") (pintype "passive"))
      (node (ref "U13") (pin "AD11") (pinfunction "VDD_AD11") (pintype "passive"))
      (node (ref "U13") (pin "AD13") (pinfunction "VDD_AD13") (pintype "passive"))
      (node (ref "U13") (pin "AD15") (pinfunction "VDD_AD15") (pintype "passive"))
      (node (ref "U13") (pin "AD17") (pinfunction "VDD_AD17") (pintype "passive"))
      (node (ref "U13") (pin "AD19") (pinfunction "VDD_AD19") (pintype "passive"))
      (node (ref "U13") (pin "AD21") (pinfunction "VDD_AD21") (pintype "passive"))
      (node (ref "U13") (pin "AD23") (pinfunction "VDD_AD23") (pintype "passive"))
      (node (ref "U13") (pin "AD25") (pinfunction "VDD_AD25") (pintype "passive"))
      (node (ref "U13") (pin "AD27") (pinfunction "VDD_AD27") (pintype "passive"))
      (node (ref "U13") (pin "AD29") (pinfunction "VDD_AD29") (pintype "passive"))
      (node (ref "U13") (pin "AD3") (pinfunction "VDD_AD3") (pintype "passive"))
      (node (ref "U13") (pin "AD5") (pinfunction "VDD_AD5") (pintype "passive"))
      (node (ref "U13") (pin "AD7") (pinfunction "VDD_AD7") (pintype "passive"))
      (node (ref "U13") (pin "AD9") (pinfunction "VDD_AD9") (pintype "passive"))
      (node (ref "U13") (pin "AE10") (pinfunction "VDD_AE10") (pintype "passive"))
      (node (ref "U13") (pin "AE12") (pinfunction "VDD_AE12") (pintype "passive"))
      (node (ref "U13") (pin "AE14") (pinfunction "VDD_AE14") (pintype "passive"))
      (node (ref "U13") (pin "AE16") (pinfunction "VDD_AE16") (pintype "passive"))
      (node (ref "U13") (pin "AE18") (pinfunction "VDD_AE18") (pintype "passive"))
      (node (ref "U13") (pin "AE2") (pinfunction "VDD_AE2") (pintype "passive"))
      (node (ref "U13") (pin "AE20") (pinfunction "VDD_AE20") (pintype "passive"))
      (node (ref "U13") (pin "AE22") (pinfunction "VDD_AE22") (pintype "passive"))
      (node (ref "U13") (pin "AE24") (pinfunction "VDD_AE24") (pintype "passive"))
      (node (ref "U13") (pin "AE26") (pinfunction "VDD_AE26") (pintype "passive"))
      (node (ref "U13") (pin "AE28") (pinfunction "VDD_AE28") (pintype "passive"))
      (node (ref "U13") (pin "AE30") (pinfunction "VDD_AE30") (pintype "passive"))
      (node (ref "U13") (pin "AE4") (pinfunction "VDD_AE4") (pintype "passive"))
      (node (ref "U13") (pin "AE6") (pinfunction "VDD_AE6") (pintype "passive"))
      (node (ref "U13") (pin "AE8") (pinfunction "VDD_AE8") (pintype "passive"))
      (node (ref "U13") (pin "AF1") (pinfunction "VDD_AF1") (pintype "passive"))
      (node (ref "U13") (pin "AF11") (pinfunction "VDD_AF11") (pintype "passive"))
      (node (ref "U13") (pin "AF13") (pinfunction "VDD_AF13") (pintype "passive"))
      (node (ref "U13") (pin "AF15") (pinfunction "VDD_AF15") (pintype "passive"))
      (node (ref "U13") (pin "AF17") (pinfunction "VDD_AF17") (pintype "passive"))
      (node (ref "U13") (pin "AF19") (pinfunction "VDD_AF19") (pintype "passive"))
      (node (ref "U13") (pin "AF21") (pinfunction "VDD_AF21") (pintype "passive"))
      (node (ref "U13") (pin "AF23") (pinfunction "VDD_AF23") (pintype "passive"))
      (node (ref "U13") (pin "AF25") (pinfunction "VDD_AF25") (pintype "passive"))
      (node (ref "U13") (pin "AF27") (pinfunction "VDD_AF27") (pintype "passive"))
      (node (ref "U13") (pin "AF29") (pinfunction "VDD_AF29") (pintype "passive"))
      (node (ref "U13") (pin "AF3") (pinfunction "VDD_AF3") (pintype "passive"))
      (node (ref "U13") (pin "AF5") (pinfunction "VDD_AF5") (pintype "passive"))
      (node (ref "U13") (pin "AF7") (pinfunction "VDD_AF7") (pintype "passive"))
      (node (ref "U13") (pin "AF9") (pinfunction "VDD_AF9") (pintype "passive"))
      (node (ref "U13") (pin "AG10") (pinfunction "VDD_AG10") (pintype "passive"))
      (node (ref "U13") (pin "AG12") (pinfunction "VDD_AG12") (pintype "passive"))
      (node (ref "U13") (pin "AG14") (pinfunction "VDD_AG14") (pintype "passive"))
      (node (ref "U13") (pin "AG16") (pinfunction "VDD_AG16") (pintype "passive"))
      (node (ref "U13") (pin "AG18") (pinfunction "VDD_AG18") (pintype "passive"))
      (node (ref "U13") (pin "AG2") (pinfunction "VDD_AG2") (pintype "passive"))
      (node (ref "U13") (pin "AG20") (pinfunction "VDD_AG20") (pintype "passive"))
      (node (ref "U13") (pin "AG22") (pinfunction "VDD_AG22") (pintype "passive"))
      (node (ref "U13") (pin "AG24") (pinfunction "VDD_AG24") (pintype "passive"))
      (node (ref "U13") (pin "AG26") (pinfunction "VDD_AG26") (pintype "passive"))
      (node (ref "U13") (pin "AG28") (pinfunction "VDD_AG28") (pintype "passive"))
      (node (ref "U13") (pin "AG30") (pinfunction "VDD_AG30") (pintype "passive"))
      (node (ref "U13") (pin "AG4") (pinfunction "VDD_AG4") (pintype "passive"))
      (node (ref "U13") (pin "AG6") (pinfunction "VDD_AG6") (pintype "passive"))
      (node (ref "U13") (pin "AG8") (pinfunction "VDD_AG8") (pintype "passive"))
      (node (ref "U13") (pin "AH1") (pinfunction "VDD_AH1") (pintype "passive"))
      (node (ref "U13") (pin "AH11") (pinfunction "VDD_AH11") (pintype "passive"))
      (node (ref "U13") (pin "AH13") (pinfunction "VDD_AH13") (pintype "passive"))
      (node (ref "U13") (pin "AH15") (pinfunction "VDD_AH15") (pintype "passive"))
      (node (ref "U13") (pin "AH17") (pinfunction "VDD_AH17") (pintype "passive"))
      (node (ref "U13") (pin "AH19") (pinfunction "VDD_AH19") (pintype "passive"))
      (node (ref "U13") (pin "AH21") (pinfunction "VDD_AH21") (pintype "passive"))
      (node (ref "U13") (pin "AH23") (pinfunction "VDD_AH23") (pintype "passive"))
      (node (ref "U13") (pin "AH25") (pinfunction "VDD_AH25") (pintype "passive"))
      (node (ref "U13") (pin "AH27") (pinfunction "VDD_AH27") (pintype "passive"))
      (node (ref "U13") (pin "AH29") (pinfunction "VDD_AH29") (pintype "passive"))
      (node (ref "U13") (pin "AH3") (pinfunction "VDD_AH3") (pintype "passive"))
      (node (ref "U13") (pin "AH5") (pinfunction "VDD_AH5") (pintype "passive"))
      (node (ref "U13") (pin "AH7") (pinfunction "VDD_AH7") (pintype "passive"))
      (node (ref "U13") (pin "AH9") (pinfunction "VDD_AH9") (pintype "passive"))
      (node (ref "U13") (pin "AJ10") (pinfunction "VDD_AJ10") (pintype "passive"))
      (node (ref "U13") (pin "AJ14") (pinfunction "VDD_AJ14") (pintype "passive"))
      (node (ref "U13") (pin "AJ18") (pinfunction "VDD_AJ18") (pintype "passive"))
      (node (ref "U13") (pin "AJ2") (pinfunction "VDD_AJ2") (pintype "passive"))
      (node (ref "U13") (pin "AJ28") (pinfunction "VDD_AJ28") (pintype "passive"))
      (node (ref "U13") (pin "AJ30") (pinfunction "VDD_AJ30") (pintype "passive"))
      (node (ref "U13") (pin "AK1") (pinfunction "VDD_AK1") (pintype "passive"))
      (node (ref "U13") (pin "AK26") (pinfunction "VDD_AK26") (pintype "passive"))
      (node (ref "U13") (pin "AK29") (pinfunction "VDD_AK29") (pintype "passive"))
      (node (ref "U13") (pin "B1") (pinfunction "VDD_B1") (pintype "passive"))
      (node (ref "U13") (pin "B11") (pinfunction "VDD_B11") (pintype "passive"))
      (node (ref "U13") (pin "B13") (pinfunction "VDD_B13") (pintype "passive"))
      (node (ref "U13") (pin "B15") (pinfunction "VDD_B15") (pintype "passive"))
      (node (ref "U13") (pin "B17") (pinfunction "VDD_B17") (pintype "passive"))
      (node (ref "U13") (pin "B19") (pinfunction "VDD_B19") (pintype "passive"))
      (node (ref "U13") (pin "B21") (pinfunction "VDD_B21") (pintype "passive"))
      (node (ref "U13") (pin "B23") (pinfunction "VDD_B23") (pintype "passive"))
      (node (ref "U13") (pin "B25") (pinfunction "VDD_B25") (pintype "passive"))
      (node (ref "U13") (pin "B27") (pinfunction "VDD_B27") (pintype "passive"))
      (node (ref "U13") (pin "B29") (pinfunction "VDD_B29") (pintype "passive"))
      (node (ref "U13") (pin "B3") (pinfunction "VDD_B3") (pintype "passive"))
      (node (ref "U13") (pin "B5") (pinfunction "VDD_B5") (pintype "passive"))
      (node (ref "U13") (pin "B7") (pinfunction "VDD_B7") (pintype "passive"))
      (node (ref "U13") (pin "B9") (pinfunction "VDD_B9") (pintype "passive"))
      (node (ref "U13") (pin "C10") (pinfunction "VDD_C10") (pintype "passive"))
      (node (ref "U13") (pin "C12") (pinfunction "VDD_C12") (pintype "passive"))
      (node (ref "U13") (pin "C14") (pinfunction "VDD_C14") (pintype "passive"))
      (node (ref "U13") (pin "C16") (pinfunction "VDD_C16") (pintype "passive"))
      (node (ref "U13") (pin "C18") (pinfunction "VDD_C18") (pintype "passive"))
      (node (ref "U13") (pin "C2") (pinfunction "VDD_C2") (pintype "passive"))
      (node (ref "U13") (pin "C20") (pinfunction "VDD_C20") (pintype "passive"))
      (node (ref "U13") (pin "C22") (pinfunction "VDD_C22") (pintype "passive"))
      (node (ref "U13") (pin "C24") (pinfunction "VDD_C24") (pintype "passive"))
      (node (ref "U13") (pin "C26") (pinfunction "VDD_C26") (pintype "passive"))
      (node (ref "U13") (pin "C28") (pinfunction "VDD_C28") (pintype "passive"))
      (node (ref "U13") (pin "C30") (pinfunction "VDD_C30") (pintype "passive"))
      (node (ref "U13") (pin "C4") (pinfunction "VDD_C4") (pintype "passive"))
      (node (ref "U13") (pin "C6") (pinfunction "VDD_C6") (pintype "passive"))
      (node (ref "U13") (pin "C8") (pinfunction "VDD_C8") (pintype "passive"))
      (node (ref "U13") (pin "D1") (pinfunction "VDD_D1") (pintype "passive"))
      (node (ref "U13") (pin "D11") (pinfunction "VDD_D11") (pintype "passive"))
      (node (ref "U13") (pin "D13") (pinfunction "VDD_D13") (pintype "passive"))
      (node (ref "U13") (pin "D15") (pinfunction "VDD_D15") (pintype "passive"))
      (node (ref "U13") (pin "D17") (pinfunction "VDD_D17") (pintype "passive"))
      (node (ref "U13") (pin "D19") (pinfunction "VDD_D19") (pintype "passive"))
      (node (ref "U13") (pin "D21") (pinfunction "VDD_D21") (pintype "passive"))
      (node (ref "U13") (pin "D23") (pinfunction "VDD_D23") (pintype "passive"))
      (node (ref "U13") (pin "D25") (pinfunction "VDD_D25") (pintype "passive"))
      (node (ref "U13") (pin "D27") (pinfunction "VDD_D27") (pintype "passive"))
      (node (ref "U13") (pin "D29") (pinfunction "VDD_D29") (pintype "passive"))
      (node (ref "U13") (pin "D3") (pinfunction "VDD_D3") (pintype "passive"))
      (node (ref "U13") (pin "D5") (pinfunction "VDD_D5") (pintype "passive"))
      (node (ref "U13") (pin "D7") (pinfunction "VDD_D7") (pintype "passive"))
      (node (ref "U13") (pin "D9") (pinfunction "VDD_D9") (pintype "passive"))
      (node (ref "U13") (pin "E10") (pinfunction "VDD_E10") (pintype "passive"))
      (node (ref "U13") (pin "E12") (pinfunction "VDD_E12") (pintype "passive"))
      (node (ref "U13") (pin "E14") (pinfunction "VDD_E14") (pintype "passive"))
      (node (ref "U13") (pin "E16") (pinfunction "VDD_E16") (pintype "passive"))
      (node (ref "U13") (pin "E18") (pinfunction "VDD_E18") (pintype "passive"))
      (node (ref "U13") (pin "E2") (pinfunction "VDD_E2") (pintype "passive"))
      (node (ref "U13") (pin "E20") (pinfunction "VDD_E20") (pintype "passive"))
      (node (ref "U13") (pin "E22") (pinfunction "VDD_E22") (pintype "passive"))
      (node (ref "U13") (pin "E24") (pinfunction "VDD_E24") (pintype "passive"))
      (node (ref "U13") (pin "E26") (pinfunction "VDD_E26") (pintype "passive"))
      (node (ref "U13") (pin "E28") (pinfunction "VDD_E28") (pintype "passive"))
      (node (ref "U13") (pin "E30") (pinfunction "VDD_E30") (pintype "passive"))
      (node (ref "U13") (pin "E4") (pinfunction "VDD_E4") (pintype "passive"))
      (node (ref "U13") (pin "E6") (pinfunction "VDD_E6") (pintype "passive"))
      (node (ref "U13") (pin "E8") (pinfunction "VDD_E8") (pintype "passive"))
      (node (ref "U13") (pin "F1") (pinfunction "VDD_F1") (pintype "passive"))
      (node (ref "U13") (pin "F11") (pinfunction "VDD_F11") (pintype "passive"))
      (node (ref "U13") (pin "F13") (pinfunction "VDD_F13") (pintype "passive"))
      (node (ref "U13") (pin "F15") (pinfunction "VDD_F15") (pintype "passive"))
      (node (ref "U13") (pin "F17") (pinfunction "VDD_F17") (pintype "passive"))
      (node (ref "U13") (pin "F19") (pinfunction "VDD_F19") (pintype "passive"))
      (node (ref "U13") (pin "F21") (pinfunction "VDD_F21") (pintype "passive"))
      (node (ref "U13") (pin "F23") (pinfunction "VDD_F23") (pintype "passive"))
      (node (ref "U13") (pin "F25") (pinfunction "VDD_F25") (pintype "passive"))
      (node (ref "U13") (pin "F27") (pinfunction "VDD_F27") (pintype "passive"))
      (node (ref "U13") (pin "F29") (pinfunction "VDD_F29") (pintype "passive"))
      (node (ref "U13") (pin "F3") (pinfunction "VDD_F3") (pintype "passive"))
      (node (ref "U13") (pin "F5") (pinfunction "VDD_F5") (pintype "passive"))
      (node (ref "U13") (pin "F7") (pinfunction "VDD_F7") (pintype "passive"))
      (node (ref "U13") (pin "F9") (pinfunction "VDD_F9") (pintype "passive"))
      (node (ref "U13") (pin "G10") (pinfunction "VDD_G10") (pintype "passive"))
      (node (ref "U13") (pin "G12") (pinfunction "VDD_G12") (pintype "passive"))
      (node (ref "U13") (pin "G14") (pinfunction "VDD_G14") (pintype "passive"))
      (node (ref "U13") (pin "G16") (pinfunction "VDD_G16") (pintype "passive"))
      (node (ref "U13") (pin "G18") (pinfunction "VDD_G18") (pintype "passive"))
      (node (ref "U13") (pin "G2") (pinfunction "VDD_G2") (pintype "passive"))
      (node (ref "U13") (pin "G20") (pinfunction "VDD_G20") (pintype "passive"))
      (node (ref "U13") (pin "G22") (pinfunction "VDD_G22") (pintype "passive"))
      (node (ref "U13") (pin "G24") (pinfunction "VDD_G24") (pintype "passive"))
      (node (ref "U13") (pin "G26") (pinfunction "VDD_G26") (pintype "passive"))
      (node (ref "U13") (pin "G28") (pinfunction "VDD_G28") (pintype "passive"))
      (node (ref "U13") (pin "G30") (pinfunction "VDD_G30") (pintype "passive"))
      (node (ref "U13") (pin "G4") (pinfunction "VDD_G4") (pintype "passive"))
      (node (ref "U13") (pin "G6") (pinfunction "VDD_G6") (pintype "passive"))
      (node (ref "U13") (pin "G8") (pinfunction "VDD_G8") (pintype "passive"))
      (node (ref "U13") (pin "H1") (pinfunction "VDD_H1") (pintype "passive"))
      (node (ref "U13") (pin "H11") (pinfunction "VDD_H11") (pintype "passive"))
      (node (ref "U13") (pin "H13") (pinfunction "VDD_H13") (pintype "passive"))
      (node (ref "U13") (pin "H15") (pinfunction "VDD_H15") (pintype "passive"))
      (node (ref "U13") (pin "H17") (pinfunction "VDD_H17") (pintype "passive"))
      (node (ref "U13") (pin "H19") (pinfunction "VDD_H19") (pintype "passive"))
      (node (ref "U13") (pin "H21") (pinfunction "VDD_H21") (pintype "passive"))
      (node (ref "U13") (pin "H23") (pinfunction "VDD_H23") (pintype "passive"))
      (node (ref "U13") (pin "H25") (pinfunction "VDD_H25") (pintype "passive"))
      (node (ref "U13") (pin "H27") (pinfunction "VDD_H27") (pintype "passive"))
      (node (ref "U13") (pin "H29") (pinfunction "VDD_H29") (pintype "passive"))
      (node (ref "U13") (pin "H3") (pinfunction "VDD_H3") (pintype "passive"))
      (node (ref "U13") (pin "H5") (pinfunction "VDD_H5") (pintype "passive"))
      (node (ref "U13") (pin "H7") (pinfunction "VDD_H7") (pintype "passive"))
      (node (ref "U13") (pin "H9") (pinfunction "VDD_H9") (pintype "passive"))
      (node (ref "U13") (pin "J10") (pinfunction "VDD_J10") (pintype "passive"))
      (node (ref "U13") (pin "J12") (pinfunction "VDD_J12") (pintype "passive"))
      (node (ref "U13") (pin "J14") (pinfunction "VDD_J14") (pintype "passive"))
      (node (ref "U13") (pin "J16") (pinfunction "VDD_J16") (pintype "passive"))
      (node (ref "U13") (pin "J18") (pinfunction "VDD_J18") (pintype "passive"))
      (node (ref "U13") (pin "J2") (pinfunction "VDD_J2") (pintype "passive"))
      (node (ref "U13") (pin "J20") (pinfunction "VDD_J20") (pintype "passive"))
      (node (ref "U13") (pin "J22") (pinfunction "VDD_J22") (pintype "passive"))
      (node (ref "U13") (pin "J24") (pinfunction "VDD_J24") (pintype "passive"))
      (node (ref "U13") (pin "J26") (pinfunction "VDD_J26") (pintype "passive"))
      (node (ref "U13") (pin "J28") (pinfunction "VDD_J28") (pintype "passive"))
      (node (ref "U13") (pin "J30") (pinfunction "VDD_J30") (pintype "passive"))
      (node (ref "U13") (pin "J4") (pinfunction "VDD_J4") (pintype "passive"))
      (node (ref "U13") (pin "J6") (pinfunction "VDD_J6") (pintype "passive"))
      (node (ref "U13") (pin "J8") (pinfunction "VDD_J8") (pintype "passive"))
      (node (ref "U13") (pin "K1") (pinfunction "VDD_K1") (pintype "passive"))
      (node (ref "U13") (pin "K11") (pinfunction "VDD_K11") (pintype "passive"))
      (node (ref "U13") (pin "K13") (pinfunction "VDD_K13") (pintype "passive"))
      (node (ref "U13") (pin "K15") (pinfunction "VDD_K15") (pintype "passive"))
      (node (ref "U13") (pin "K17") (pinfunction "VDD_K17") (pintype "passive"))
      (node (ref "U13") (pin "K19") (pinfunction "VDD_K19") (pintype "passive"))
      (node (ref "U13") (pin "K21") (pinfunction "VDD_K21") (pintype "passive"))
      (node (ref "U13") (pin "K23") (pinfunction "VDD_K23") (pintype "passive"))
      (node (ref "U13") (pin "K25") (pinfunction "VDD_K25") (pintype "passive"))
      (node (ref "U13") (pin "K27") (pinfunction "VDD_K27") (pintype "passive"))
      (node (ref "U13") (pin "K29") (pinfunction "VDD_K29") (pintype "passive"))
      (node (ref "U13") (pin "K3") (pinfunction "VDD_K3") (pintype "passive"))
      (node (ref "U13") (pin "K5") (pinfunction "VDD_K5") (pintype "passive"))
      (node (ref "U13") (pin "K7") (pinfunction "VDD_K7") (pintype "passive"))
      (node (ref "U13") (pin "K9") (pinfunction "VDD_K9") (pintype "passive"))
      (node (ref "U13") (pin "L10") (pinfunction "VDD_L10") (pintype "passive"))
      (node (ref "U13") (pin "L12") (pinfunction "VDD_L12") (pintype "passive"))
      (node (ref "U13") (pin "L14") (pinfunction "VDD_L14") (pintype "passive"))
      (node (ref "U13") (pin "L16") (pinfunction "VDD_L16") (pintype "passive"))
      (node (ref "U13") (pin "L18") (pinfunction "VDD_L18") (pintype "passive"))
      (node (ref "U13") (pin "L2") (pinfunction "VDD_L2") (pintype "passive"))
      (node (ref "U13") (pin "L20") (pinfunction "VDD_L20") (pintype "passive"))
      (node (ref "U13") (pin "L22") (pinfunction "VDD_L22") (pintype "passive"))
      (node (ref "U13") (pin "L24") (pinfunction "VDD_L24") (pintype "passive"))
      (node (ref "U13") (pin "L26") (pinfunction "VDD_L26") (pintype "passive"))
      (node (ref "U13") (pin "L28") (pinfunction "VDD_L28") (pintype "passive"))
      (node (ref "U13") (pin "L30") (pinfunction "VDD_L30") (pintype "passive"))
      (node (ref "U13") (pin "L4") (pinfunction "VDD_L4") (pintype "passive"))
      (node (ref "U13") (pin "L6") (pinfunction "VDD_L6") (pintype "passive"))
      (node (ref "U13") (pin "L8") (pinfunction "VDD_L8") (pintype "passive"))
      (node (ref "U13") (pin "M1") (pinfunction "VDD_M1") (pintype "passive"))
      (node (ref "U13") (pin "M11") (pinfunction "VDD_M11") (pintype "passive"))
      (node (ref "U13") (pin "M13") (pinfunction "VDD_M13") (pintype "passive"))
      (node (ref "U13") (pin "M15") (pinfunction "VDD_M15") (pintype "passive"))
      (node (ref "U13") (pin "M17") (pinfunction "VDD_M17") (pintype "passive"))
      (node (ref "U13") (pin "M19") (pinfunction "VDD_M19") (pintype "passive"))
      (node (ref "U13") (pin "M21") (pinfunction "VDD_M21") (pintype "passive"))
      (node (ref "U13") (pin "M23") (pinfunction "VDD_M23") (pintype "passive"))
      (node (ref "U13") (pin "M25") (pinfunction "VDD_M25") (pintype "passive"))
      (node (ref "U13") (pin "M27") (pinfunction "VDD_M27") (pintype "passive"))
      (node (ref "U13") (pin "M29") (pinfunction "VDD_M29") (pintype "passive"))
      (node (ref "U13") (pin "M3") (pinfunction "VDD_M3") (pintype "passive"))
      (node (ref "U13") (pin "M5") (pinfunction "VDD_M5") (pintype "passive"))
      (node (ref "U13") (pin "M7") (pinfunction "VDD_M7") (pintype "passive"))
      (node (ref "U13") (pin "M9") (pinfunction "VDD_M9") (pintype "passive"))
      (node (ref "U13") (pin "N10") (pinfunction "VDD_N10") (pintype "passive"))
      (node (ref "U13") (pin "N12") (pinfunction "VDD_N12") (pintype "passive"))
      (node (ref "U13") (pin "N14") (pinfunction "VDD_N14") (pintype "passive"))
      (node (ref "U13") (pin "N16") (pinfunction "VDD_N16") (pintype "passive"))
      (node (ref "U13") (pin "N18") (pinfunction "VDD_N18") (pintype "passive"))
      (node (ref "U13") (pin "N2") (pinfunction "VDD_N2") (pintype "passive"))
      (node (ref "U13") (pin "N20") (pinfunction "VDD_N20") (pintype "passive"))
      (node (ref "U13") (pin "N22") (pinfunction "VDD_N22") (pintype "passive"))
      (node (ref "U13") (pin "N24") (pinfunction "VDD_N24") (pintype "passive"))
      (node (ref "U13") (pin "N26") (pinfunction "VDD_N26") (pintype "passive"))
      (node (ref "U13") (pin "N28") (pinfunction "VDD_N28") (pintype "passive"))
      (node (ref "U13") (pin "N30") (pinfunction "VDD_N30") (pintype "passive"))
      (node (ref "U13") (pin "N4") (pinfunction "VDD_N4") (pintype "passive"))
      (node (ref "U13") (pin "N6") (pinfunction "VDD_N6") (pintype "passive"))
      (node (ref "U13") (pin "N8") (pinfunction "VDD_N8") (pintype "passive"))
      (node (ref "U13") (pin "P1") (pinfunction "VDD_P1") (pintype "passive"))
      (node (ref "U13") (pin "P11") (pinfunction "VDD_P11") (pintype "passive"))
      (node (ref "U13") (pin "P13") (pinfunction "VDD_P13") (pintype "passive"))
      (node (ref "U13") (pin "P15") (pinfunction "VDD_P15") (pintype "passive"))
      (node (ref "U13") (pin "P17") (pinfunction "VDD_P17") (pintype "passive"))
      (node (ref "U13") (pin "P19") (pinfunction "VDD_P19") (pintype "passive"))
      (node (ref "U13") (pin "P21") (pinfunction "VDD_P21") (pintype "passive"))
      (node (ref "U13") (pin "P23") (pinfunction "VDD_P23") (pintype "passive"))
      (node (ref "U13") (pin "P25") (pinfunction "VDD_P25") (pintype "passive"))
      (node (ref "U13") (pin "P27") (pinfunction "VDD_P27") (pintype "passive"))
      (node (ref "U13") (pin "P29") (pinfunction "VDD_P29") (pintype "passive"))
      (node (ref "U13") (pin "P3") (pinfunction "VDD_P3") (pintype "passive"))
      (node (ref "U13") (pin "P5") (pinfunction "VDD_P5") (pintype "passive"))
      (node (ref "U13") (pin "P7") (pinfunction "VDD_P7") (pintype "passive"))
      (node (ref "U13") (pin "P9") (pinfunction "VDD_P9") (pintype "passive"))
      (node (ref "U13") (pin "R10") (pinfunction "VDD_R10") (pintype "passive"))
      (node (ref "U13") (pin "R12") (pinfunction "VDD_R12") (pintype "passive"))
      (node (ref "U13") (pin "R14") (pinfunction "VDD_R14") (pintype "passive"))
      (node (ref "U13") (pin "R16") (pinfunction "VDD_R16") (pintype "passive"))
      (node (ref "U13") (pin "R18") (pinfunction "VDD_R18") (pintype "passive"))
      (node (ref "U13") (pin "R2") (pinfunction "VDD_R2") (pintype "passive"))
      (node (ref "U13") (pin "R20") (pinfunction "VDD_R20") (pintype "passive"))
      (node (ref "U13") (pin "R22") (pinfunction "VDD_R22") (pintype "passive"))
      (node (ref "U13") (pin "R24") (pinfunction "VDD_R24") (pintype "passive"))
      (node (ref "U13") (pin "R26") (pinfunction "VDD_R26") (pintype "passive"))
      (node (ref "U13") (pin "R28") (pinfunction "VDD_R28") (pintype "passive"))
      (node (ref "U13") (pin "R30") (pinfunction "VDD_R30") (pintype "passive"))
      (node (ref "U13") (pin "R4") (pinfunction "VDD_R4") (pintype "passive"))
      (node (ref "U13") (pin "R6") (pinfunction "VDD_R6") (pintype "passive"))
      (node (ref "U13") (pin "R8") (pinfunction "VDD_R8") (pintype "passive"))
      (node (ref "U13") (pin "T1") (pinfunction "VDD_T1") (pintype "passive"))
      (node (ref "U13") (pin "T11") (pinfunction "VDD_T11") (pintype "passive"))
      (node (ref "U13") (pin "T13") (pinfunction "VDD_T13") (pintype "passive"))
      (node (ref "U13") (pin "T15") (pinfunction "VDD_T15") (pintype "passive"))
      (node (ref "U13") (pin "T17") (pinfunction "VDD_T17") (pintype "passive"))
      (node (ref "U13") (pin "T19") (pinfunction "VDD_T19") (pintype "passive"))
      (node (ref "U13") (pin "T21") (pinfunction "VDD_T21") (pintype "passive"))
      (node (ref "U13") (pin "T23") (pinfunction "VDD_T23") (pintype "passive"))
      (node (ref "U13") (pin "T25") (pinfunction "VDD_T25") (pintype "passive"))
      (node (ref "U13") (pin "T27") (pinfunction "VDD_T27") (pintype "passive"))
      (node (ref "U13") (pin "T29") (pinfunction "VDD_T29") (pintype "passive"))
      (node (ref "U13") (pin "T3") (pinfunction "VDD_T3") (pintype "passive"))
      (node (ref "U13") (pin "T5") (pinfunction "VDD_T5") (pintype "passive"))
      (node (ref "U13") (pin "T7") (pinfunction "VDD_T7") (pintype "passive"))
      (node (ref "U13") (pin "T9") (pinfunction "VDD_T9") (pintype "passive"))
      (node (ref "U13") (pin "U10") (pinfunction "VDD_U10") (pintype "passive"))
      (node (ref "U13") (pin "U12") (pinfunction "VDD_U12") (pintype "passive"))
      (node (ref "U13") (pin "U14") (pinfunction "VDD_U14") (pintype "passive"))
      (node (ref "U13") (pin "U16") (pinfunction "VDD_U16") (pintype "passive"))
      (node (ref "U13") (pin "U18") (pinfunction "VDD_U18") (pintype "passive"))
      (node (ref "U13") (pin "U2") (pinfunction "VDD_U2") (pintype "passive"))
      (node (ref "U13") (pin "U20") (pinfunction "VDD_U20") (pintype "passive"))
      (node (ref "U13") (pin "U22") (pinfunction "VDD_U22") (pintype "passive"))
      (node (ref "U13") (pin "U24") (pinfunction "VDD_U24") (pintype "passive"))
      (node (ref "U13") (pin "U26") (pinfunction "VDD_U26") (pintype "passive"))
      (node (ref "U13") (pin "U28") (pinfunction "VDD_U28") (pintype "passive"))
      (node (ref "U13") (pin "U30") (pinfunction "VDD_U30") (pintype "passive"))
      (node (ref "U13") (pin "U4") (pinfunction "VDD_U4") (pintype "passive"))
      (node (ref "U13") (pin "U6") (pinfunction "VDD_U6") (pintype "passive"))
      (node (ref "U13") (pin "U8") (pinfunction "VDD_U8") (pintype "passive"))
      (node (ref "U13") (pin "V1") (pinfunction "VDD_V1") (pintype "passive"))
      (node (ref "U13") (pin "V11") (pinfunction "VDD_V11") (pintype "passive"))
      (node (ref "U13") (pin "V13") (pinfunction "VDD_V13") (pintype "passive"))
      (node (ref "U13") (pin "V15") (pinfunction "VDD_V15") (pintype "passive"))
      (node (ref "U13") (pin "V17") (pinfunction "VDD_V17") (pintype "passive"))
      (node (ref "U13") (pin "V19") (pinfunction "VDD_V19") (pintype "passive"))
      (node (ref "U13") (pin "V21") (pinfunction "VDD_V21") (pintype "passive"))
      (node (ref "U13") (pin "V23") (pinfunction "VDD_V23") (pintype "passive"))
      (node (ref "U13") (pin "V25") (pinfunction "VDD_V25") (pintype "passive"))
      (node (ref "U13") (pin "V27") (pinfunction "VDD_V27") (pintype "passive"))
      (node (ref "U13") (pin "V29") (pinfunction "VDD_V29") (pintype "passive"))
      (node (ref "U13") (pin "V3") (pinfunction "VDD_V3") (pintype "passive"))
      (node (ref "U13") (pin "V5") (pinfunction "VDD_V5") (pintype "passive"))
      (node (ref "U13") (pin "V7") (pinfunction "VDD_V7") (pintype "passive"))
      (node (ref "U13") (pin "V9") (pinfunction "VDD_V9") (pintype "passive"))
      (node (ref "U13") (pin "W10") (pinfunction "VDD_W10") (pintype "passive"))
      (node (ref "U13") (pin "W12") (pinfunction "VDD_W12") (pintype "passive"))
      (node (ref "U13") (pin "W14") (pinfunction "VDD_W14") (pintype "passive"))
      (node (ref "U13") (pin "W16") (pinfunction "VDD_W16") (pintype "passive"))
      (node (ref "U13") (pin "W18") (pinfunction "VDD_W18") (pintype "passive"))
      (node (ref "U13") (pin "W2") (pinfunction "VDD_W2") (pintype "passive"))
      (node (ref "U13") (pin "W20") (pinfunction "VDD_W20") (pintype "passive"))
      (node (ref "U13") (pin "W22") (pinfunction "VDD_W22") (pintype "passive"))
      (node (ref "U13") (pin "W24") (pinfunction "VDD_W24") (pintype "passive"))
      (node (ref "U13") (pin "W26") (pinfunction "VDD_W26") (pintype "passive"))
      (node (ref "U13") (pin "W28") (pinfunction "VDD_W28") (pintype "passive"))
      (node (ref "U13") (pin "W30") (pinfunction "VDD_W30") (pintype "passive"))
      (node (ref "U13") (pin "W4") (pinfunction "VDD_W4") (pintype "passive"))
      (node (ref "U13") (pin "W6") (pinfunction "VDD_W6") (pintype "passive"))
      (node (ref "U13") (pin "W8") (pinfunction "VDD_W8") (pintype "passive"))
      (node (ref "U13") (pin "Y1") (pinfunction "VDD_Y1") (pintype "passive"))
      (node (ref "U13") (pin "Y11") (pinfunction "VDD_Y11") (pintype "passive"))
      (node (ref "U13") (pin "Y13") (pinfunction "VDD_Y13") (pintype "passive"))
      (node (ref "U13") (pin "Y15") (pinfunction "VDD_Y15") (pintype "passive"))
      (node (ref "U13") (pin "Y17") (pinfunction "VDD_Y17") (pintype "passive"))
      (node (ref "U13") (pin "Y19") (pinfunction "VDD_Y19") (pintype "passive"))
      (node (ref "U13") (pin "Y21") (pinfunction "VDD_Y21") (pintype "passive"))
      (node (ref "U13") (pin "Y23") (pinfunction "VDD_Y23") (pintype "passive"))
      (node (ref "U13") (pin "Y25") (pinfunction "VDD_Y25") (pintype "passive"))
      (node (ref "U13") (pin "Y27") (pinfunction "VDD_Y27") (pintype "passive"))
      (node (ref "U13") (pin "Y29") (pinfunction "VDD_Y29") (pintype "passive"))
      (node (ref "U13") (pin "Y3") (pinfunction "VDD_Y3") (pintype "passive"))
      (node (ref "U13") (pin "Y5") (pinfunction "VDD_Y5") (pintype "passive"))
      (node (ref "U13") (pin "Y7") (pinfunction "VDD_Y7") (pintype "passive"))
      (node (ref "U13") (pin "Y9") (pinfunction "VDD_Y9") (pintype "passive"))
    )
    (net (code "2") (name "GND") (class "Default")
      (node (ref "C103") (pin "1") (pinfunction "1_1") (pintype "passive"))
      (node (ref "C104") (pin "1") (pinfunction "1_1") (pintype "passive"))
      (node (ref "C105") (pin "1") (pinfunction "1_1") (pintype "passive"))
      (node (ref "C106") (pin "1") (pinfunction "1_1") (pintype "passive"))
      (node (ref "C107") (pin "1") (pinfunction "1_1") (pintype "passive"))
      (node (ref "C129") (pin "1") (pinfunction "1_1") (pintype "passive"))
      (node (ref "C135") (pin "1") (pinfunction "1_1") (pintype "passive"))
      (node (ref "C136") (pin "1") (pinfunction "1_1") (pintype "passive"))
      (node (ref "C137") (pin "1") (pinfunction "1_1") (pintype "passive"))
      (node (ref "C142") (pin "1") (pinfunction "1_1") (pintype "passive"))
      (node (ref "C143") (pin "1") (pinfunction "1_1") (pintype "passive"))
      (node (ref "C144") (pin "1") (pinfunction "1_1") (pintype "passive"))
      (node (ref "C145") (pin "1") (pinfunction "1_1") (pintype "passive"))
      (node (ref "C146") (pin "1") (pinfunction "1_1") (pintype "passive"))
      (node (ref "C147") (pin "1") (pinfunction "1_1") (pintype "passive"))
      (node (ref "C148") (pin "1") (pinfunction "1_1") (pintype "passive"))
      (node (ref "C149") (pin "1") (pinfunction "1_1") (pintype "passive"))
      (node (ref "C150") (pin "1") (pinfunction "1_1") (pintype "passive"))
      (node (ref "C151") (pin "1") (pinfunction "1_1") (pintype "passive"))
      (node (ref "C152") (pin "1") (pinfunction "1_1") (pintype "passive"))
      (node (ref "C153") (pin "1") (pinfunction "1_1") (pintype "passive"))
      (node (ref "C154") (pin "1") (pinfunction "1_1") (pintype "passive"))
      (node (ref "C155") (pin "1") (pinfunction "1_1") (pintype "passive"))
      (node (ref "C156") (pin "1") (pinfunction "1_1") (pintype "passive"))
      (node (ref "C157") (pin "1") (pinfunction "1_1") (pintype "passive"))
      (node (ref "C158") (pin "1") (pinfunction "1_1") (pintype "passive"))
      (node (ref "C159") (pin "1") (pinfunction "1_1") (pintype "passive"))
      (node (ref "C160") (pin "1") (pinfunction "1_1") (pintype "passive"))
      (node (ref "C161") (pin "1") (pinfunction "1_1") (pintype "passive"))
      (node (ref "C162") (pin "1") (pinfunction "1_1") (pintype "passive"))
      (node (ref "C163") (pin "1") (pinfunction "1_1") (pintype "passive"))
      (node (ref "C164") (pin "1") (pinfunction "1_1") (pintype "passive"))
      (node (ref "C165") (pin "1") (pinfunction "1_1") (pintype "passive"))
      (node (ref "C166") (pin "1") (pinfunction "1_1") (pintype "passive"))
      (node (ref "C167") (pin "1") (pinfunction "1_1") (pintype "passive"))
      (node (ref "C168") (pin "1") (pinfunction "1_1") (pintype "passive"))
      (node (ref "C169") (pin "1") (pinfunction "1_1") (pintype "passive"))
      (node (ref "C171") (pin "1") (pinfunction "1_1") (pintype "passive"))
      (node (ref "C177") (pin "1") (pinfunction "1_1") (pintype "passive"))
      (node (ref "C178") (pin "1") (pinfunction "1_1") (pintype "passive"))
      (node (ref "C179") (pin "1") (pinfunction "1_1") (pintype "passive"))
      (node (ref "C18") (pin "1") (pinfunction "1_1") (pintype "passive"))
      (node (ref "C180") (pin "1") (pinfunction "1_1") (pintype "passive"))
      (node (ref "C181") (pin "1") (pinfunction "1_1") (pintype "passive"))
      (node (ref "C182") (pin "1") (pinfunction "1_1") (pintype "passive"))
      (node (ref "C183") (pin "1") (pinfunction "1_1") (pintype "passive"))
      (node (ref "C184") (pin "1") (pinfunction "1_1") (pintype "passive"))
      (node (ref "C185") (pin "1") (pinfunction "1_1") (pintype "passive"))
      (node (ref "C186") (pin "1") (pinfunction "1_1") (pintype "passive"))
      (node (ref "C188") (pin "1") (pinfunction "1_1") (pintype "passive"))
      (node (ref "C189") (pin "1") (pinfunction "1_1") (pintype "passive"))
      (node (ref "C19") (pin "1") (pinfunction "1_1") (pintype "passive"))
      (node (ref "C190") (pin "1") (pinfunction "1_1") (pintype "passive"))
      (node (ref "C191") (pin "1") (pinfunction "1_1") (pintype "passive"))
      (node (ref "C192") (pin "1") (pinfunction "1_1") (pintype "passive"))
      (node (ref "C193") (pin "1") (pinfunction "1_1") (pintype "passive"))
      (node (ref "C194") (pin "1") (pinfunction "1_1") (pintype "passive"))
      (node (ref "C195") (pin "1") (pinfunction "1_1") (pintype "passive"))
      (node (ref "C196") (pin "1") (pinfunction "1_1") (pintype "passive"))
      (node (ref "C198") (pin "1") (pinfunction "1_1") (pintype "passive"))
      (node (ref "C201") (pin "1") (pinfunction "1_1") (pintype "passive"))
      (node (ref "C204") (pin "1") (pinfunction "1_1") (pintype "passive"))
      (node (ref "C206") (pin "1") (pinfunction "1_1") (pintype "passive"))
      (node (ref "C207") (pin "1") (pinfunction "1_1") (pintype "passive"))
      (node (ref "C208") (pin "1") (pinfunction "1_1") (pintype "passive"))
      (node (ref "C209") (pin "1") (pinfunction "1_1") (pintype "passive"))
      (node (ref "C210") (pin "1") (pinfunction "1_1") (pintype "passive"))
      (node (ref "C211") (pin "1") (pinfunction "1_1") (pintype "passive"))
      (node (ref "C212") (pin "1") (pinfunction "1_1") (pintype "passive"))
      (node (ref "C213") (pin "1") (pinfunction "1_1") (pintype "passive"))
      (node (ref "C214") (pin "1") (pinfunction "1_1") (pintype "passive"))
      (node (ref "C215") (pin "1") (pinfunction "1_1") (pintype "passive"))
      (node (ref "C216") (pin "1") (pinfunction "1_1") (pintype "passive"))
      (node (ref "C217") (pin "1") (pinfunction "1_1") (pintype "passive"))
      (node (ref "C218") (pin "1") (pinfunction "1_1") (pintype "passive"))
      (node (ref "C219") (pin "1") (pinfunction "1_1") (pintype "passive"))
      (node (ref "C220") (pin "1") (pinfunction "1_1") (pintype "passive"))
      (node (ref "C221") (pin "1") (pinfunction "1_1") (pintype "passive"))
      (node (ref "C222") (pin "1") (pinfunction "1_1") (pintype "passive"))
      (node (ref "C223") (pin "1") (pinfunction "1_1") (pintype "passive"))
      (node (ref "C224") (pin "1") (pinfunction "1_1") (pintype "passive"))
      (node (ref "C225") (pin "1") (pinfunction "1_1") (pintype "passive"))
      (node (ref "C34") (pin "1") (pinfunction "1_1") (pintype "passive"))
      (node (ref "C35") (pin "1") (pinfunction "1_1") (pintype "passive"))
      (node (ref "C36") (pin "1") (pinfunction "1_1") (pintype "passive"))
      (node (ref "C4") (pin "1") (pinfunction "1_1") (pintype "passive"))
      (node (ref "C44") (pin "1") (pinfunction "1_1") (pintype "passive"))
      (node (ref "C45") (pin "1") (pinfunction "1_1") (pintype "passive"))
      (node (ref "C46") (pin "1") (pinfunction "1_1") (pintype "passive"))
      (node (ref "C48") (pin "1") (pinfunction "1_1") (pintype "passive"))
      (node (ref "C53") (pin "1") (pinfunction "1_1") (pintype "passive"))
      (node (ref "C55") (pin "1") (pinfunction "1_1") (pintype "passive"))
      (node (ref "C56") (pin "1") (pinfunction "1_1") (pintype "passive"))
      (node (ref "C57") (pin "1") (pinfunction "1_1") (pintype "passive"))
      (node (ref "C59") (pin "1") (pinfunction "1_1") (pintype "passive"))
      (node (ref "C60") (pin "1") (pinfunction "1_1") (pintype "passive"))
      (node (ref "C61") (pin "1") (pinfunction "1_1") (pintype "passive"))
      (node (ref "C62") (pin "1") (pinfunction "1_1") (pintype "passive"))
      (node (ref "C63") (pin "1") (pinfunction "1_1") (pintype "passive"))
      (node (ref "C64") (pin "1") (pinfunction "1_1") (pintype "passive"))
      (node (ref "C72") (pin "1") (pinfunction "1_1") (pintype "passive"))
      (node (ref "C73") (pin "1") (pinfunction "1_1") (pintype "passive"))
      (node (ref "C74") (pin "1") (pinfunction "1_1") (pintype "passive"))
      (node (ref "C75") (pin "1") (pinfunction "1_1") (pintype "passive"))
      (node (ref "C76") (pin "1") (pinfunction "1_1") (pintype "passive"))
      (node (ref "C77") (pin "1") (pinfunction "1_1") (pintype "passive"))
      (node (ref "C78") (pin "1") (pinfunction "1_1") (pintype "passive"))
      (node (ref "C79") (pin "1") (pinfunction "1_1") (pintype "passive"))
      (node (ref "C80") (pin "1") (pinfunction "1_1") (pintype "passive"))
      (node (ref "C81") (pin "1") (pinfunction "1_1") (pintype "passive"))
      (node (ref "C82") (pin "1") (pinfunction "1_1") (pintype "passive"))
      (node (ref "C83") (pin "1") (pinfunction "1_1") (pintype "passive"))
      (node (ref "C84") (pin "1") (pinfunction "1_1") (pintype "passive"))
      (node (ref "C86") (pin "1") (pinfunction "1_1") (pintype "passive"))
      (node (ref "C87") (pin "1") (pinfunction "1_1") (pintype "passive"))
      (node (ref "C88") (pin "1") (pinfunction "1_1") (pintype "passive"))
      (node (ref "C90") (pin "1") (pinfunction "1_1") (pintype "passive"))
      (node (ref "C91") (pin "1") (pinfunction "1_1") (pintype "passive"))
      (node (ref "C94") (pin "1") (pinfunction "1_1") (pintype "passive"))
      (node (ref "C95") (pin "1") (pinfunction "1_1") (pintype "passive"))
      (node (ref "U13") (pin "A1") (pinfunction "GND_A1") (pintype "passive"))
      (node (ref "U13") (pin "A11") (pinfunction "GND_A11") (pintype "passive"))
      (node (ref "U13") (pin "A13") (pinfunction "GND_A13") (pintype "passive"))
      (node (ref "U13") (pin "A15") (pinfunction "GND_A15") (pintype "passive"))
      (node (ref "U13") (pin "A17") (pinfunction "GND_A17") (pintype "passive"))
      (node (ref "U13") (pin "A19") (pinfunction "GND_A19") (pintype "passive"))
      (node (ref "U13") (pin "A21") (pinfunction "GND_A21") (pintype "passive"))
      (node (ref "U13") (pin "A23") (pinfunction "GND_A23") (pintype "passive"))
      (node (ref "U13") (pin "A25") (pinfunction "GND_A25") (pintype "passive"))
      (node (ref "U13") (pin "A27") (pinfunction "GND_A27") (pintype "passive"))
      (node (ref "U13") (pin "A29") (pinfunction "GND_A29") (pintype "passive"))
      (node (ref "U13") (pin "A3") (pinfunction "GND_A3") (pintype "passive"))
      (node (ref "U13") (pin "A5") (pinfunction "GND_A5") (pintype "passive"))
      (node (ref "U13") (pin "A7") (pinfunction "GND_A7") (pintype "passive"))
      (node (ref "U13") (pin "A9") (pinfunction "GND_A9") (pintype "passive"))
      (node (ref "U13") (pin "AA1") (pinfunction "GND_AA1") (pintype "passive"))
      (node (ref "U13") (pin "AA11") (pinfunction "GND_AA11") (pintype "passive"))
      (node (ref "U13") (pin "AA13") (pinfunction "GND_AA13") (pintype "passive"))
      (node (ref "U13") (pin "AA15") (pinfunction "GND_AA15") (pintype "passive"))
      (node (ref "U13") (pin "AA17") (pinfunction "GND_AA17") (pintype "passive"))
      (node (ref "U13") (pin "AA19") (pinfunction "GND_AA19") (pintype "passive"))
      (node (ref "U13") (pin "AA21") (pinfunction "GND_AA21") (pintype "passive"))
      (node (ref "U13") (pin "AA23") (pinfunction "GND_AA23") (pintype "passive"))
      (node (ref "U13") (pin "AA25") (pinfunction "GND_AA25") (pintype "passive"))
      (node (ref "U13") (pin "AA27") (pinfunction "GND_AA27") (pintype "passive"))
      (node (ref "U13") (pin "AA29") (pinfunction "GND_AA29") (pintype "passive"))
      (node (ref "U13") (pin "AA3") (pinfunction "GND_AA3") (pintype "passive"))
      (node (ref "U13") (pin "AA5") (pinfunction "GND_AA5") (pintype "passive"))
      (node (ref "U13") (pin "AA7") (pinfunction "GND_AA7") (pintype "passive"))
      (node (ref "U13") (pin "AA9") (pinfunction "GND_AA9") (pintype "passive"))
      (node (ref "U13") (pin "AB10") (pinfunction "GND_AB10") (pintype "passive"))
      (node (ref "U13") (pin "AB12") (pinfunction "GND_AB12") (pintype "passive"))
      (node (ref "U13") (pin "AB14") (pinfunction "GND_AB14") (pintype "passive"))
      (node (ref "U13") (pin "AB16") (pinfunction "GND_AB16") (pintype "passive"))
      (node (ref "U13") (pin "AB18") (pinfunction "GND_AB18") (pintype "passive"))
      (node (ref "U13") (pin "AB2") (pinfunction "GND_AB2") (pintype "passive"))
      (node (ref "U13") (pin "AB20") (pinfunction "GND_AB20") (pintype "passive"))
      (node (ref "U13") (pin "AB22") (pinfunction "GND_AB22") (pintype "passive"))
      (node (ref "U13") (pin "AB24") (pinfunction "GND_AB24") (pintype "passive"))
      (node (ref "U13") (pin "AB26") (pinfunction "GND_AB26") (pintype "passive"))
      (node (ref "U13") (pin "AB28") (pinfunction "GND_AB28") (pintype "passive"))
      (node (ref "U13") (pin "AB30") (pinfunction "GND_AB30") (pintype "passive"))
      (node (ref "U13") (pin "AB4") (pinfunction "GND_AB4") (pintype "passive"))
      (node (ref "U13") (pin "AB6") (pinfunction "GND_AB6") (pintype "passive"))
      (node (ref "U13") (pin "AB8") (pinfunction "GND_AB8") (pintype "passive"))
      (node (ref "U13") (pin "AC1") (pinfunction "GND_AC1") (pintype "passive"))
      (node (ref "U13") (pin "AC11") (pinfunction "GND_AC11") (pintype "passive"))
      (node (ref "U13") (pin "AC13") (pinfunction "GND_AC13") (pintype "passive"))
      (node (ref "U13") (pin "AC15") (pinfunction "GND_AC15") (pintype "passive"))
      (node (ref "U13") (pin "AC17") (pinfunction "GND_AC17") (pintype "passive"))
      (node (ref "U13") (pin "AC19") (pinfunction "GND_AC19") (pintype "passive"))
      (node (ref "U13") (pin "AC21") (pinfunction "GND_AC21") (pintype "passive"))
      (node (ref "U13") (pin "AC23") (pinfunction "GND_AC23") (pintype "passive"))
      (node (ref "U13") (pin "AC25") (pinfunction "GND_AC25") (pintype "passive"))
      (node (ref "U13") (pin "AC27") (pinfunction "GND_AC27") (pintype "passive"))
      (node (ref "U13") (pin "AC29") (pinfunction "GND_AC29") (pintype "passive"))
      (node (ref "U13") (pin "AC3") (pinfunction "GND_AC3") (pintype "passive"))
      (node (ref "U13") (pin "AC5") (pinfunction "GND_AC5") (pintype "passive"))
      (node (ref "U13") (pin "AC7") (pinfunction "GND_AC7") (pintype "passive"))
      (node (ref "U13") (pin "AC9") (pinfunction "GND_AC9") (pintype "passive"))
      (node (ref "U13") (pin "AD10") (pinfunction "GND_AD10") (pintype "passive"))
      (node (ref "U13") (pin "AD12") (pinfunction "GND_AD12") (pintype "passive"))
      (node (ref "U13") (pin "AD14") (pinfunction "GND_AD14") (pintype "passive"))
      (node (ref "U13") (pin "AD16") (pinfunction "GND_AD16") (pintype "passive"))
      (node (ref "U13") (pin "AD18") (pinfunction "GND_AD18") (pintype "passive"))
      (node (ref "U13") (pin "AD2") (pinfunction "GND_AD2") (pintype "passive"))
      (node (ref "U13") (pin "AD20") (pinfunction "GND_AD20") (pintype "passive"))
      (node (ref "U13") (pin "AD22") (pinfunction "GND_AD22") (pintype "passive"))
      (node (ref "U13") (pin "AD24") (pinfunction "GND_AD24") (pintype "passive"))
      (node (ref "U13") (pin "AD26") (pinfunction "GND_AD26") (pintype "passive"))
      (node (ref "U13") (pin "AD28") (pinfunction "GND_AD28") (pintype "passive"))
      (node (ref "U13") (pin "AD30") (pinfunction "GND_AD30") (pintype "passive"))
      (node (ref "U13") (pin "AD4") (pinfunction "GND_AD4") (pintype "passive"))
      (node (ref "U13") (pin "AD6") (pinfunction "GND_AD6") (pintype "passive"))
      (node (ref "U13") (pin "AD8") (pinfunction "GND_AD8") (pintype "passive"))
      (node (ref "U13") (pin "AE1") (pinfunction "GND_AE1") (pintype "passive"))
      (node (ref "U13") (pin "AE11") (pinfunction "GND_AE11") (pintype "passive"))
      (node (ref "U13") (pin "AE13") (pinfunction "GND_AE13") (pintype "passive"))
      (node (ref "U13") (pin "AE15") (pinfunction "GND_AE15") (pintype "passive"))
      (node (ref "U13") (pin "AE17") (pinfunction "GND_AE17") (pintype "passive"))
      (node (ref "U13") (pin "AE19") (pinfunction "GND_AE19") (pintype "passive"))
      (node (ref "U13") (pin "AE21") (pinfunction "GND_AE21") (pintype "passive"))
      (node (ref "U13") (pin "AE23") (pinfunction "GND_AE23") (pintype "passive"))
      (node (ref "U13") (pin "AE25") (pinfunction "GND_AE25") (pintype "passive"))
      (node (ref "U13") (pin "AE27") (pinfunction "GND_AE27") (pintype "passive"))
      (node (ref "U13") (pin "AE29") (pinfunction "GND_AE29") (pintype "passive"))
      (node (ref "U13") (pin "AE3") (pinfunction "GND_AE3") (pintype "passive"))
      (node (ref "U13") (pin "AE5") (pinfunction "GND_AE5") (pintype "passive"))
      (node (ref "U13") (pin "AE7") (pinfunction "GND_AE7") (pintype "passive"))
      (node (ref "U13") (pin "AE9") (pinfunction "GND_AE9") (pintype "passive"))
      (node (ref "U13") (pin "AF10") (pinfunction "GND_AF10") (pintype "passive"))
      (node (ref "U13") (pin "AF12") (pinfunction "GND_AF12") (pintype "passive"))
      (node (ref "U13") (pin "AF14") (pinfunction "GND_AF14") (pintype "passive"))
      (node (ref "U13") (pin "AF16") (pinfunction "GND_AF16") (pintype "passive"))
      (node (ref "U13") (pin "AF18") (pinfunction "GND_AF18") (pintype "passive"))
      (node (ref "U13") (pin "AF2") (pinfunction "GND_AF2") (pintype "passive"))
      (node (ref "U13") (pin "AF20") (pinfunction "GND_AF20") (pintype "passive"))
      (node (ref "U13") (pin "AF22") (pinfunction "GND_AF22") (pintype "passive"))
      (node (ref "U13") (pin "AF24") (pinfunction "GND_AF24") (pintype "passive"))
      (node (ref "U13") (pin "AF26") (pinfunction "GND_AF26") (pintype "passive"))
      (node (ref "U13") (pin "AF28") (pinfunction "GND_AF28") (pintype "passive"))
      (node (ref "U13") (pin "AF30") (pinfunction "GND_AF30") (pintype "passive"))
      (node (ref "U13") (pin "AF4") (pinfunction "GND_AF4") (pintype "passive"))
      (node (ref "U13") (pin "AF6") (pinfunction "GND_AF6") (pintype "passive"))
      (node (ref "U13") (pin "AF8") (pinfunction "GND_AF8") (pintype "passive"))
      (node (ref "U13") (pin "AG1") (pinfunction "GND_AG1") (pintype "passive"))
      (node (ref "U13") (pin "AG11") (pinfunction "GND_AG11") (pintype "passive"))
      (node (ref "U13") (pin "AG13") (pinfunction "GND_AG13") (pintype "passive"))
      (node (ref "U13") (pin "AG15") (pinfunction "GND_AG15") (pintype "passive"))
      (node (ref "U13") (pin "AG17") (pinfunction "GND_AG17") (pintype "passive"))
      (node (ref "U13") (pin "AG19") (pinfunction "GND_AG19") (pintype "passive"))
      (node (ref "U13") (pin "AG21") (pinfunction "GND_AG21") (pintype "passive"))
      (node (ref "U13") (pin "AG23") (pinfunction "GND_AG23") (pintype "passive"))
      (node (ref "U13") (pin "AG25") (pinfunction "GND_AG25") (pintype "passive"))
      (node (ref "U13") (pin "AG27") (pinfunction "GND_AG27") (pintype "passive"))
      (node (ref "U13") (pin "AG29") (pinfunction "GND_AG29") (pintype "passive"))
      (node (ref "U13") (pin "AG3") (pinfunction "GND_AG3") (pintype "passive"))
      (node (ref "U13") (pin "AG5") (pinfunction "GND_AG5") (pintype "passive"))
      (node (ref "U13") (pin "AG7") (pinfunction "GND_AG7") (pintype "passive"))
      (node (ref "U13") (pin "AG9") (pinfunction "GND_AG9") (pintype "passive"))
      (node (ref "U13") (pin "AH10") (pinfunction "GND_AH10") (pintype "passive"))
      (node (ref "U13") (pin "AH12") (pinfunction "GND_AH12") (pintype "passive"))
      (node (ref "U13") (pin "AH14") (pinfunction "GND_AH14") (pintype "passive"))
      (node (ref "U13") (pin "AH16") (pinfunction "GND_AH16") (pintype "passive"))
      (node (ref "U13") (pin "AH18") (pinfunction "GND_AH18") (pintype "passive"))
      (node (ref "U13") (pin "AH2") (pinfunction "GND_AH2") (pintype "passive"))
      (node (ref "U13") (pin "AH20") (pinfunction "GND_AH20") (pintype "passive"))
      (node (ref "U13") (pin "AH22") (pinfunction "GND_AH22") (pintype "passive"))
      (node (ref "U13") (pin "AH24") (pinfunction "GND_AH24") (pintype "passive"))
      (node (ref "U13") (pin "AH26") (pinfunction "GND_AH26") (pintype "passive"))
      (node (ref "U13") (pin "AH28") (pinfunction "GND_AH28") (pintype "passive"))
      (node (ref "U13") (pin "AH30") (pinfunction "GND_AH30") (pintype "passive"))
      (node (ref "U13") (pin "AH4") (pinfunction "GND_AH4") (pintype "passive"))
      (node (ref "U13") (pin "AH6") (pinfunction "GND_AH6") (pintype "passive"))
      (node (ref "U13") (pin "AH8") (pinfunction "GND_AH8") (pintype "passive"))
      (node (ref "U13") (pin "AJ1") (pinfunction "GND_AJ1") (pintype "passive"))
      (node (ref "U13") (pin "AJ11") (pinfunction "GND_AJ11") (pintype "passive"))
      (node (ref "U13") (pin "AJ17") (pinfunction "GND_AJ17") (pintype "passive"))
      (node (ref "U13") (pin "AJ27") (pinfunction "GND_AJ27") (pintype "passive"))
      (node (ref "U13") (pin "AJ29") (pinfunction "GND_AJ29") (pintype "passive"))
      (node (ref "U13") (pin "AJ3") (pinfunction "GND_AJ3") (pintype "passive"))
      (node (ref "U13") (pin "AJ4") (pinfunction "GND_AJ4") (pintype "passive"))
      (node (ref "U13") (pin "AJ6") (pinfunction "GND_AJ6") (pintype "passive"))
      (node (ref "U13") (pin "AJ9") (pinfunction "GND_AJ9") (pintype "passive"))
      (node (ref "U13") (pin "AK14") (pinfunction "GND_AK14") (pintype "passive"))
      (node (ref "U13") (pin "AK17") (pinfunction "GND_AK17") (pintype "passive"))
      (node (ref "U13") (pin "AK2") (pinfunction "GND_AK2") (pintype "passive"))
      (node (ref "U13") (pin "AK20") (pinfunction "GND_AK20") (pintype "passive"))
      (node (ref "U13") (pin "AK23") (pinfunction "GND_AK23") (pintype "passive"))
      (node (ref "U13") (pin "AK30") (pinfunction "GND_AK30") (pintype "passive"))
      (node (ref "U13") (pin "B10") (pinfunction "GND_B10") (pintype "passive"))
      (node (ref "U13") (pin "B12") (pinfunction "GND_B12") (pintype "passive"))
      (node (ref "U13") (pin "B14") (pinfunction "GND_B14") (pintype "passive"))
      (node (ref "U13") (pin "B16") (pinfunction "GND_B16") (pintype "passive"))
      (node (ref "U13") (pin "B18") (pinfunction "GND_B18") (pintype "passive"))
      (node (ref "U13") (pin "B2") (pinfunction "GND_B2") (pintype "passive"))
      (node (ref "U13") (pin "B20") (pinfunction "GND_B20") (pintype "passive"))
      (node (ref "U13") (pin "B22") (pinfunction "GND_B22") (pintype "passive"))
      (node (ref "U13") (pin "B24") (pinfunction "GND_B24") (pintype "passive"))
      (node (ref "U13") (pin "B26") (pinfunction "GND_B26") (pintype "passive"))
      (node (ref "U13") (pin "B28") (pinfunction "GND_B28") (pintype "passive"))
      (node (ref "U13") (pin "B30") (pinfunction "GND_B30") (pintype "passive"))
      (node (ref "U13") (pin "B4") (pinfunction "GND_B4") (pintype "passive"))
      (node (ref "U13") (pin "B6") (pinfunction "GND_B6") (pintype "passive"))
      (node (ref "U13") (pin "B8") (pinfunction "GND_B8") (pintype "passive"))
      (node (ref "U13") (pin "C1") (pinfunction "GND_C1") (pintype "passive"))
      (node (ref "U13") (pin "C11") (pinfunction "GND_C11") (pintype "passive"))
      (node (ref "U13") (pin "C13") (pinfunction "GND_C13") (pintype "passive"))
      (node (ref "U13") (pin "C15") (pinfunction "GND_C15") (pintype "passive"))
      (node (ref "U13") (pin "C17") (pinfunction "GND_C17") (pintype "passive"))
      (node (ref "U13") (pin "C19") (pinfunction "GND_C19") (pintype "passive"))
      (node (ref "U13") (pin "C21") (pinfunction "GND_C21") (pintype "passive"))
      (node (ref "U13") (pin "C23") (pinfunction "GND_C23") (pintype "passive"))
      (node (ref "U13") (pin "C25") (pinfunction "GND_C25") (pintype "passive"))
      (node (ref "U13") (pin "C27") (pinfunction "GND_C27") (pintype "passive"))
      (node (ref "U13") (pin "C29") (pinfunction "GND_C29") (pintype "passive"))
      (node (ref "U13") (pin "C3") (pinfunction "GND_C3") (pintype "passive"))
      (node (ref "U13") (pin "C5") (pinfunction "GND_C5") (pintype "passive"))
      (node (ref "U13") (pin "C7") (pinfunction "GND_C7") (pintype "passive"))
      (node (ref "U13") (pin "C9") (pinfunction "GND_C9") (pintype "passive"))
      (node (ref "U13") (pin "D10") (pinfunction "GND_D10") (pintype "passive"))
      (node (ref "U13") (pin "D12") (pinfunction "GND_D12") (pintype "passive"))
      (node (ref "U13") (pin "D14") (pinfunction "GND_D14") (pintype "passive"))
      (node (ref "U13") (pin "D16") (pinfunction "GND_D16") (pintype "passive"))
      (node (ref "U13") (pin "D18") (pinfunction "GND_D18") (pintype "passive"))
      (node (ref "U13") (pin "D2") (pinfunction "GND_D2") (pintype "passive"))
      (node (ref "U13") (pin "D20") (pinfunction "GND_D20") (pintype "passive"))
      (node (ref "U13") (pin "D22") (pinfunction "GND_D22") (pintype "passive"))
      (node (ref "U13") (pin "D24") (pinfunction "GND_D24") (pintype "passive"))
      (node (ref "U13") (pin "D26") (pinfunction "GND_D26") (pintype "passive"))
      (node (ref "U13") (pin "D28") (pinfunction "GND_D28") (pintype "passive"))
      (node (ref "U13") (pin "D30") (pinfunction "GND_D30") (pintype "passive"))
      (node (ref "U13") (pin "D4") (pinfunction "GND_D4") (pintype "passive"))
      (node (ref "U13") (pin "D6") (pinfunction "GND_D6") (pintype "passive"))
      (node (ref "U13") (pin "D8") (pinfunction "GND_D8") (pintype "passive"))
      (node (ref "U13") (pin "E1") (pinfunction "GND_E1") (pintype "passive"))
      (node (ref "U13") (pin "E11") (pinfunction "GND_E11") (pintype "passive"))
      (node (ref "U13") (pin "E13") (pinfunction "GND_E13") (pintype "passive"))
      (node (ref "U13") (pin "E15") (pinfunction "GND_E15") (pintype "passive"))
      (node (ref "U13") (pin "E17") (pinfunction "GND_E17") (pintype "passive"))
      (node (ref "U13") (pin "E19") (pinfunction "GND_E19") (pintype "passive"))
      (node (ref "U13") (pin "E21") (pinfunction "GND_E21") (pintype "passive"))
      (node (ref "U13") (pin "E23") (pinfunction "GND_E23") (pintype "passive"))
      (node (ref "U13") (pin "E25") (pinfunction "GND_E25") (pintype "passive"))
      (node (ref "U13") (pin "E27") (pinfunction "GND_E27") (pintype "passive"))
      (node (ref "U13") (pin "E29") (pinfunction "GND_E29") (pintype "passive"))
      (node (ref "U13") (pin "E3") (pinfunction "GND_E3") (pintype "passive"))
      (node (ref "U13") (pin "E5") (pinfunction "GND_E5") (pintype "passive"))
      (node (ref "U13") (pin "E7") (pinfunction "GND_E7") (pintype "passive"))
      (node (ref "U13") (pin "E9") (pinfunction "GND_E9") (pintype "passive"))
      (node (ref "U13") (pin "F10") (pinfunction "GND_F10") (pintype "passive"))
      (node (ref "U13") (pin "F12") (pinfunction "GND_F12") (pintype "passive"))
      (node (ref "U13") (pin "F14") (pinfunction "GND_F14") (pintype "passive"))
      (node (ref "U13") (pin "F16") (pinfunction "GND_F16") (pintype "passive"))
      (node (ref "U13") (pin "F18") (pinfunction "GND_F18") (pintype "passive"))
      (node (ref "U13") (pin "F2") (pinfunction "GND_F2") (pintype "passive"))
      (node (ref "U13") (pin "F20") (pinfunction "GND_F20") (pintype "passive"))
      (node (ref "U13") (pin "F22") (pinfunction "GND_F22") (pintype "passive"))
      (node (ref "U13") (pin "F24") (pinfunction "GND_F24") (pintype "passive"))
      (node (ref "U13") (pin "F26") (pinfunction "GND_F26") (pintype "passive"))
      (node (ref "U13") (pin "F28") (pinfunction "GND_F28") (pintype "passive"))
      (node (ref "U13") (pin "F30") (pinfunction "GND_F30") (pintype "passive"))
      (node (ref "U13") (pin "F4") (pinfunction "GND_F4") (pintype "passive"))
      (node (ref "U13") (pin "F6") (pinfunction "GND_F6") (pintype "passive"))
      (node (ref "U13") (pin "F8") (pinfunction "GND_F8") (pintype "passive"))
      (node (ref "U13") (pin "G1") (pinfunction "GND_G1") (pintype "passive"))
      (node (ref "U13") (pin "G11") (pinfunction "GND_G11") (pintype "passive"))
      (node (ref "U13") (pin "G13") (pinfunction "GND_G13") (pintype "passive"))
      (node (ref "U13") (pin "G15") (pinfunction "GND_G15") (pintype "passive"))
      (node (ref "U13") (pin "G17") (pinfunction "GND_G17") (pintype "passive"))
      (node (ref "U13") (pin "G19") (pinfunction "GND_G19") (pintype "passive"))
      (node (ref "U13") (pin "G21") (pinfunction "GND_G21") (pintype "passive"))
      (node (ref "U13") (pin "G23") (pinfunction "GND_G23") (pintype "passive"))
      (node (ref "U13") (pin "G25") (pinfunction "GND_G25") (pintype "passive"))
      (node (ref "U13") (pin "G27") (pinfunction "GND_G27") (pintype "passive"))
      (node (ref "U13") (pin "G29") (pinfunction "GND_G29") (pintype "passive"))
      (node (ref "U13") (pin "G3") (pinfunction "GND_G3") (pintype "passive"))
      (node (ref "U13") (pin "G5") (pinfunction "GND_G5") (pintype "passive"))
      (node (ref "U13") (pin "G7") (pinfunction "GND_G7") (pintype "passive"))
      (node (ref "U13") (pin "G9") (pinfunction "GND_G9") (pintype "passive"))
      (node (ref "U13") (pin "H10") (pinfunction "GND_H10") (pintype "passive"))
      (node (ref "U13") (pin "H12") (pinfunction "GND_H12") (pintype "passive"))
      (node (ref "U13") (pin "H14") (pinfunction "GND_H14") (pintype "passive"))
      (node (ref "U13") (pin "H16") (pinfunction "GND_H16") (pintype "passive"))
      (node (ref "U13") (pin "H18") (pinfunction "GND_H18") (pintype "passive"))
      (node (ref "U13") (pin "H2") (pinfunction "GND_H2") (pintype "passive"))
      (node (ref "U13") (pin "H20") (pinfunction "GND_H20") (pintype "passive"))
      (node (ref "U13") (pin "H22") (pinfunction "GND_H22") (pintype "passive"))
      (node (ref "U13") (pin "H24") (pinfunction "GND_H24") (pintype "passive"))
      (node (ref "U13") (pin "H26") (pinfunction "GND_H26") (pintype "passive"))
      (node (ref "U13") (pin "H28") (pinfunction "GND_H28") (pintype "passive"))
      (node (ref "U13") (pin "H30") (pinfunction "GND_H30") (pintype "passive"))
      (node (ref "U13") (pin "H4") (pinfunction "GND_H4") (pintype "passive"))
      (node (ref "U13") (pin "H6") (pinfunction "GND_H6") (pintype "passive"))
      (node (ref "U13") (pin "H8") (pinfunction "GND_H8") (pintype "passive"))
      (node (ref "U13") (pin "J1") (pinfunction "GND_J1") (pintype "passive"))
      (node (ref "U13") (pin "J11") (pinfunction "GND_J11") (pintype "passive"))
      (node (ref "U13") (pin "J13") (pinfunction "GND_J13") (pintype "passive"))
      (node (ref "U13") (pin "J15") (pinfunction "GND_J15") (pintype "passive"))
      (node (ref "U13") (pin "J17") (pinfunction "GND_J17") (pintype "passive"))
      (node (ref "U13") (pin "J19") (pinfunction "GND_J19") (pintype "passive"))
      (node (ref "U13") (pin "J21") (pinfunction "GND_J21") (pintype "passive"))
      (node (ref "U13") (pin "J23") (pinfunction "GND_J23") (pintype "passive"))
      (node (ref "U13") (pin "J25") (pinfunction "GND_J25") (pintype "passive"))
      (node (ref "U13") (pin "J27") (pinfunction "GND_J27") (pintype "passive"))
      (node (ref "U13") (pin "J29") (pinfunction "GND_J29") (pintype "passive"))
      (node (ref "U13") (pin "J3") (pinfunction "GND_J3") (pintype "passive"))
      (node (ref "U13") (pin "J5") (pinfunction "GND_J5") (pintype "passive"))
      (node (ref "U13") (pin "J7") (pinfunction "GND_J7") (pintype "passive"))
      (node (ref "U13") (pin "J9") (pinfunction "GND_J9") (pintype "passive"))
      (node (ref "U13") (pin "K10") (pinfunction "GND_K10") (pintype "passive"))
      (node (ref "U13") (pin "K12") (pinfunction "GND_K12") (pintype "passive"))
      (node (ref "U13") (pin "K14") (pinfunction "GND_K14") (pintype "passive"))
      (node (ref "U13") (pin "K16") (pinfunction "GND_K16") (pintype "passive"))
      (node (ref "U13") (pin "K18") (pinfunction "GND_K18") (pintype "passive"))
      (node (ref "U13") (pin "K2") (pinfunction "GND_K2") (pintype "passive"))
      (node (ref "U13") (pin "K20") (pinfunction "GND_K20") (pintype "passive"))
      (node (ref "U13") (pin "K22") (pinfunction "GND_K22") (pintype "passive"))
      (node (ref "U13") (pin "K24") (pinfunction "GND_K24") (pintype "passive"))
      (node (ref "U13") (pin "K26") (pinfunction "GND_K26") (pintype "passive"))
      (node (ref "U13") (pin "K28") (pinfunction "GND_K28") (pintype "passive"))
      (node (ref "U13") (pin "K30") (pinfunction "GND_K30") (pintype "passive"))
      (node (ref "U13") (pin "K4") (pinfunction "GND_K4") (pintype "passive"))
      (node (ref "U13") (pin "K6") (pinfunction "GND_K6") (pintype "passive"))
      (node (ref "U13") (pin "K8") (pinfunction "GND_K8") (pintype "passive"))
      (node (ref "U13") (pin "L1") (pinfunction "GND_L1") (pintype "passive"))
      (node (ref "U13") (pin "L11") (pinfunction "GND_L11") (pintype "passive"))
      (node (ref "U13") (pin "L13") (pinfunction "GND_L13") (pintype "passive"))
      (node (ref "U13") (pin "L15") (pinfunction "GND_L15") (pintype "passive"))
      (node (ref "U13") (pin "L17") (pinfunction "GND_L17") (pintype "passive"))
      (node (ref "U13") (pin "L19") (pinfunction "GND_L19") (pintype "passive"))
      (node (ref "U13") (pin "L21") (pinfunction "GND_L21") (pintype "passive"))
      (node (ref "U13") (pin "L23") (pinfunction "GND_L23") (pintype "passive"))
      (node (ref "U13") (pin "L25") (pinfunction "GND_L25") (pintype "passive"))
      (node (ref "U13") (pin "L27") (pinfunction "GND_L27") (pintype "passive"))
      (node (ref "U13") (pin "L29") (pinfunction "GND_L29") (pintype "passive"))
      (node (ref "U13") (pin "L3") (pinfunction "GND_L3") (pintype "passive"))
      (node (ref "U13") (pin "L5") (pinfunction "GND_L5") (pintype "passive"))
      (node (ref "U13") (pin "L7") (pinfunction "GND_L7") (pintype "passive"))
      (node (ref "U13") (pin "L9") (pinfunction "GND_L9") (pintype "passive"))
      (node (ref "U13") (pin "M10") (pinfunction "GND_M10") (pintype "passive"))
      (node (ref "U13") (pin "M12") (pinfunction "GND_M12") (pintype "passive"))
      (node (ref "U13") (pin "M14") (pinfunction "GND_M14") (pintype "passive"))
      (node (ref "U13") (pin "M16") (pinfunction "GND_M16") (pintype "passive"))
      (node (ref "U13") (pin "M18") (pinfunction "GND_M18") (pintype "passive"))
      (node (ref "U13") (pin "M2") (pinfunction "GND_M2") (pintype "passive"))
      (node (ref "U13") (pin "M20") (pinfunction "GND_M20") (pintype "passive"))
      (node (ref "U13") (pin "M22") (pinfunction "GND_M22") (pintype "passive"))
      (node (ref "U13") (pin "M24") (pinfunction "GND_M24") (pintype "passive"))
      (node (ref "U13") (pin "M26") (pinfunction "GND_M26") (pintype "passive"))
      (node (ref "U13") (pin "M28") (pinfunction "GND_M28") (pintype "passive"))
      (node (ref "U13") (pin "M30") (pinfunction "GND_M30") (pintype "passive"))
      (node (ref "U13") (pin "M4") (pinfunction "GND_M4") (pintype "passive"))
      (node (ref "U13") (pin "M6") (pinfunction "GND_M6") (pintype "passive"))
      (node (ref "U13") (pin "M8") (pinfunction "GND_M8") (pintype "passive"))
      (node (ref "U13") (pin "N1") (pinfunction "GND_N1") (pintype "passive"))
      (node (ref "U13") (pin "N11") (pinfunction "GND_N11") (pintype "passive"))
      (node (ref "U13") (pin "N13") (pinfunction "GND_N13") (pintype "passive"))
      (node (ref "U13") (pin "N15") (pinfunction "GND_N15") (pintype "passive"))
      (node (ref "U13") (pin "N17") (pinfunction "GND_N17") (pintype "passive"))
      (node (ref "U13") (pin "N19") (pinfunction "GND_N19") (pintype "passive"))
      (node (ref "U13") (pin "N21") (pinfunction "GND_N21") (pintype "passive"))
      (node (ref "U13") (pin "N23") (pinfunction "GND_N23") (pintype "passive"))
      (node (ref "U13") (pin "N25") (pinfunction "GND_N25") (pintype "passive"))
      (node (ref "U13") (pin "N27") (pinfunction "GND_N27") (pintype "passive"))
      (node (ref "U13") (pin "N29") (pinfunction "GND_N29") (pintype "passive"))
      (node (ref "U13") (pin "N3") (pinfunction "GND_N3") (pintype "passive"))
      (node (ref "U13") (pin "N5") (pinfunction "GND_N5") (pintype "passive"))
      (node (ref "U13") (pin "N7") (pinfunction "GND_N7") (pintype "passive"))
      (node (ref "U13") (pin "N9") (pinfunction "GND_N9") (pintype "passive"))
      (node (ref "U13") (pin "P10") (pinfunction "GND_P10") (pintype "passive"))
      (node (ref "U13") (pin "P12") (pinfunction "GND_P12") (pintype "passive"))
      (node (ref "U13") (pin "P14") (pinfunction "GND_P14") (pintype "passive"))
      (node (ref "U13") (pin "P16") (pinfunction "GND_P16") (pintype "passive"))
      (node (ref "U13") (pin "P18") (pinfunction "GND_P18") (pintype "passive"))
      (node (ref "U13") (pin "P2") (pinfunction "GND_P2") (pintype "passive"))
      (node (ref "U13") (pin "P20") (pinfunction "GND_P20") (pintype "passive"))
      (node (ref "U13") (pin "P22") (pinfunction "GND_P22") (pintype "passive"))
      (node (ref "U13") (pin "P24") (pinfunction "GND_P24") (pintype "passive"))
      (node (ref "U13") (pin "P26") (pinfunction "GND_P26") (pintype "passive"))
      (node (ref "U13") (pin "P28") (pinfunction "GND_P28") (pintype "passive"))
      (node (ref "U13") (pin "P30") (pinfunction "GND_P30") (pintype "passive"))
      (node (ref "U13") (pin "P4") (pinfunction "GND_P4") (pintype "passive"))
      (node (ref "U13") (pin "P6") (pinfunction "GND_P6") (pintype "passive"))
      (node (ref "U13") (pin "P8") (pinfunction "GND_P8") (pintype "passive"))
      (node (ref "U13") (pin "R1") (pinfunction "GND_R1") (pintype "passive"))
      (node (ref "U13") (pin "R11") (pinfunction "GND_R11") (pintype "passive"))
      (node (ref "U13") (pin "R13") (pinfunction "GND_R13") (pintype "passive"))
      (node (ref "U13") (pin "R15") (pinfunction "GND_R15") (pintype "passive"))
      (node (ref "U13") (pin "R17") (pinfunction "GND_R17") (pintype "passive"))
      (node (ref "U13") (pin "R19") (pinfunction "GND_R19") (pintype "passive"))
      (node (ref "U13") (pin "R21") (pinfunction "GND_R21") (pintype "passive"))
      (node (ref "U13") (pin "R23") (pinfunction "GND_R23") (pintype "passive"))
      (node (ref "U13") (pin "R25") (pinfunction "GND_R25") (pintype "passive"))
      (node (ref "U13") (pin "R27") (pinfunction "GND_R27") (pintype "passive"))
      (node (ref "U13") (pin "R29") (pinfunction "GND_R29") (pintype "passive"))
      (node (ref "U13") (pin "R3") (pinfunction "GND_R3") (pintype "passive"))
      (node (ref "U13") (pin "R5") (pinfunction "GND_R5") (pintype "passive"))
      (node (ref "U13") (pin "R7") (pinfunction "GND_R7") (pintype "passive"))
      (node (ref "U13") (pin "R9") (pinfunction "GND_R9") (pintype "passive"))
      (node (ref "U13") (pin "T10") (pinfunction "GND_T10") (pintype "passive"))
      (node (ref "U13") (pin "T12") (pinfunction "GND_T12") (pintype "passive"))
      (node (ref "U13") (pin "T14") (pinfunction "GND_T14") (pintype "passive"))
      (node (ref "U13") (pin "T16") (pinfunction "GND_T16") (pintype "passive"))
      (node (ref "U13") (pin "T18") (pinfunction "GND_T18") (pintype "passive"))
      (node (ref "U13") (pin "T2") (pinfunction "GND_T2") (pintype "passive"))
      (node (ref "U13") (pin "T20") (pinfunction "GND_T20") (pintype "passive"))
      (node (ref "U13") (pin "T22") (pinfunction "GND_T22") (pintype "passive"))
      (node (ref "U13") (pin "T24") (pinfunction "GND_T24") (pintype "passive"))
      (node (ref "U13") (pin "T26") (pinfunction "GND_T26") (pintype "passive"))
      (node (ref "U13") (pin "T28") (pinfunction "GND_T28") (pintype "passive"))
      (node (ref "U13") (pin "T30") (pinfunction "GND_T30") (pintype "passive"))
      (node (ref "U13") (pin "T4") (pinfunction "GND_T4") (pintype "passive"))
      (node (ref "U13") (pin "T6") (pinfunction "GND_T6") (pintype "passive"))
      (node (ref "U13") (pin "T8") (pinfunction "GND_T8") (pintype "passive"))
      (node (ref "U13") (pin "U1") (pinfunction "GND_U1") (pintype "passive"))
      (node (ref "U13") (pin "U11") (pinfunction "GND_U11") (pintype "passive"))
      (node (ref "U13") (pin "U13") (pinfunction "GND_U13") (pintype "passive"))
      (node (ref "U13") (pin "U15") (pinfunction "GND_U15") (pintype "passive"))
      (node (ref "U13") (pin "U17") (pinfunction "GND_U17") (pintype "passive"))
      (node (ref "U13") (pin "U19") (pinfunction "GND_U19") (pintype "passive"))
      (node (ref "U13") (pin "U21") (pinfunction "GND_U21") (pintype "passive"))
      (node (ref "U13") (pin "U23") (pinfunction "GND_U23") (pintype "passive"))
      (node (ref "U13") (pin "U25") (pinfunction "GND_U25") (pintype "passive"))
      (node (ref "U13") (pin "U27") (pinfunction "GND_U27") (pintype "passive"))
      (node (ref "U13") (pin "U29") (pinfunction "GND_U29") (pintype "passive"))
      (node (ref "U13") (pin "U3") (pinfunction "GND_U3") (pintype "passive"))
      (node (ref "U13") (pin "U5") (pinfunction "GND_U5") (pintype "passive"))
      (node (ref "U13") (pin "U7") (pinfunction "GND_U7") (pintype "passive"))
      (node (ref "U13") (pin "U9") (pinfunction "GND_U9") (pintype "passive"))
      (node (ref "U13") (pin "V10") (pinfunction "GND_V10") (pintype "passive"))
      (node (ref "U13") (pin "V12") (pinfunction "GND_V12") (pintype "passive"))
      (node (ref "U13") (pin "V14") (pinfunction "GND_V14") (pintype "passive"))
      (node (ref "U13") (pin "V16") (pinfunction "GND_V16") (pintype "passive"))
      (node (ref "U13") (pin "V18") (pinfunction "GND_V18") (pintype "passive"))
      (node (ref "U13") (pin "V2") (pinfunction "GND_V2") (pintype "passive"))
      (node (ref "U13") (pin "V20") (pinfunction "GND_V20") (pintype "passive"))
      (node (ref "U13") (pin "V22") (pinfunction "GND_V22") (pintype "passive"))
      (node (ref "U13") (pin "V24") (pinfunction "GND_V24") (pintype "passive"))
      (node (ref "U13") (pin "V26") (pinfunction "GND_V26") (pintype "passive"))
      (node (ref "U13") (pin "V28") (pinfunction "GND_V28") (pintype "passive"))
      (node (ref "U13") (pin "V30") (pinfunction "GND_V30") (pintype "passive"))
      (node (ref "U13") (pin "V4") (pinfunction "GND_V4") (pintype "passive"))
      (node (ref "U13") (pin "V6") (pinfunction "GND_V6") (pintype "passive"))
      (node (ref "U13") (pin "V8") (pinfunction "GND_V8") (pintype "passive"))
      (node (ref "U13") (pin "W1") (pinfunction "GND_W1") (pintype "passive"))
      (node (ref "U13") (pin "W11") (pinfunction "GND_W11") (pintype "passive"))
      (node (ref "U13") (pin "W13") (pinfunction "GND_W13") (pintype "passive"))
      (node (ref "U13") (pin "W15") (pinfunction "GND_W15") (pintype "passive"))
      (node (ref "U13") (pin "W17") (pinfunction "GND_W17") (pintype "passive"))
      (node (ref "U13") (pin "W19") (pinfunction "GND_W19") (pintype "passive"))
      (node (ref "U13") (pin "W21") (pinfunction "GND_W21") (pintype "passive"))
      (node (ref "U13") (pin "W23") (pinfunction "GND_W23") (pintype "passive"))
      (node (ref "U13") (pin "W25") (pinfunction "GND_W25") (pintype "passive"))
      (node (ref "U13") (pin "W27") (pinfunction "GND_W27") (pintype "passive"))
      (node (ref "U13") (pin "W29") (pinfunction "GND_W29") (pintype "passive"))
      (node (ref "U13") (pin "W3") (pinfunction "GND_W3") (pintype "passive"))
      (node (ref "U13") (pin "W5") (pinfunction "GND_W5") (pintype "passive"))
      (node (ref "U13") (pin "W7") (pinfunction "GND_W7") (pintype "passive"))
      (node (ref "U13") (pin "W9") (pinfunction "GND_W9") (pintype "passive"))
      (node (ref "U13") (pin "Y10") (pinfunction "GND_Y10") (pintype "passive"))
      (node (ref "U13") (pin "Y12") (pinfunction "GND_Y12") (pintype "passive"))
      (node (ref "U13") (pin "Y14") (pinfunction "GND_Y14") (pintype "passive"))
      (node (ref "U13") (pin "Y16") (pinfunction "GND_Y16") (pintype "passive"))
      (node (ref "U13") (pin "Y18") (pinfunction "GND_Y18") (pintype "passive"))
      (node (ref "U13") (pin "Y2") (pinfunction "GND_Y2") (pintype "passive"))
      (node (ref "U13") (pin "Y20") (pinfunction "GND_Y20") (pintype "passive"))
      (node (ref "U13") (pin "Y22") (pinfunction "GND_Y22") (pintype "passive"))
      (node (ref "U13") (pin "Y24") (pinfunction "GND_Y24") (pintype "passive"))
      (node (ref "U13") (pin "Y26") (pinfunction "GND_Y26") (pintype "passive"))
      (node (ref "U13") (pin "Y28") (pinfunction "GND_Y28") (pintype "passive"))
      (node (ref "U13") (pin "Y30") (pinfunction "GND_Y30") (pintype "passive"))
      (node (ref "U13") (pin "Y4") (pinfunction "GND_Y4") (pintype "passive"))
      (node (ref "U13") (pin "Y6") (pinfunction "GND_Y6") (pintype "passive"))
      (node (ref "U13") (pin "Y8") (pinfunction "GND_Y8") (pintype "passive"))
    )
  )
)
